# XMICRO-6502_V2_1.net
KiCad netlist of a schematic drawn in EAGLE
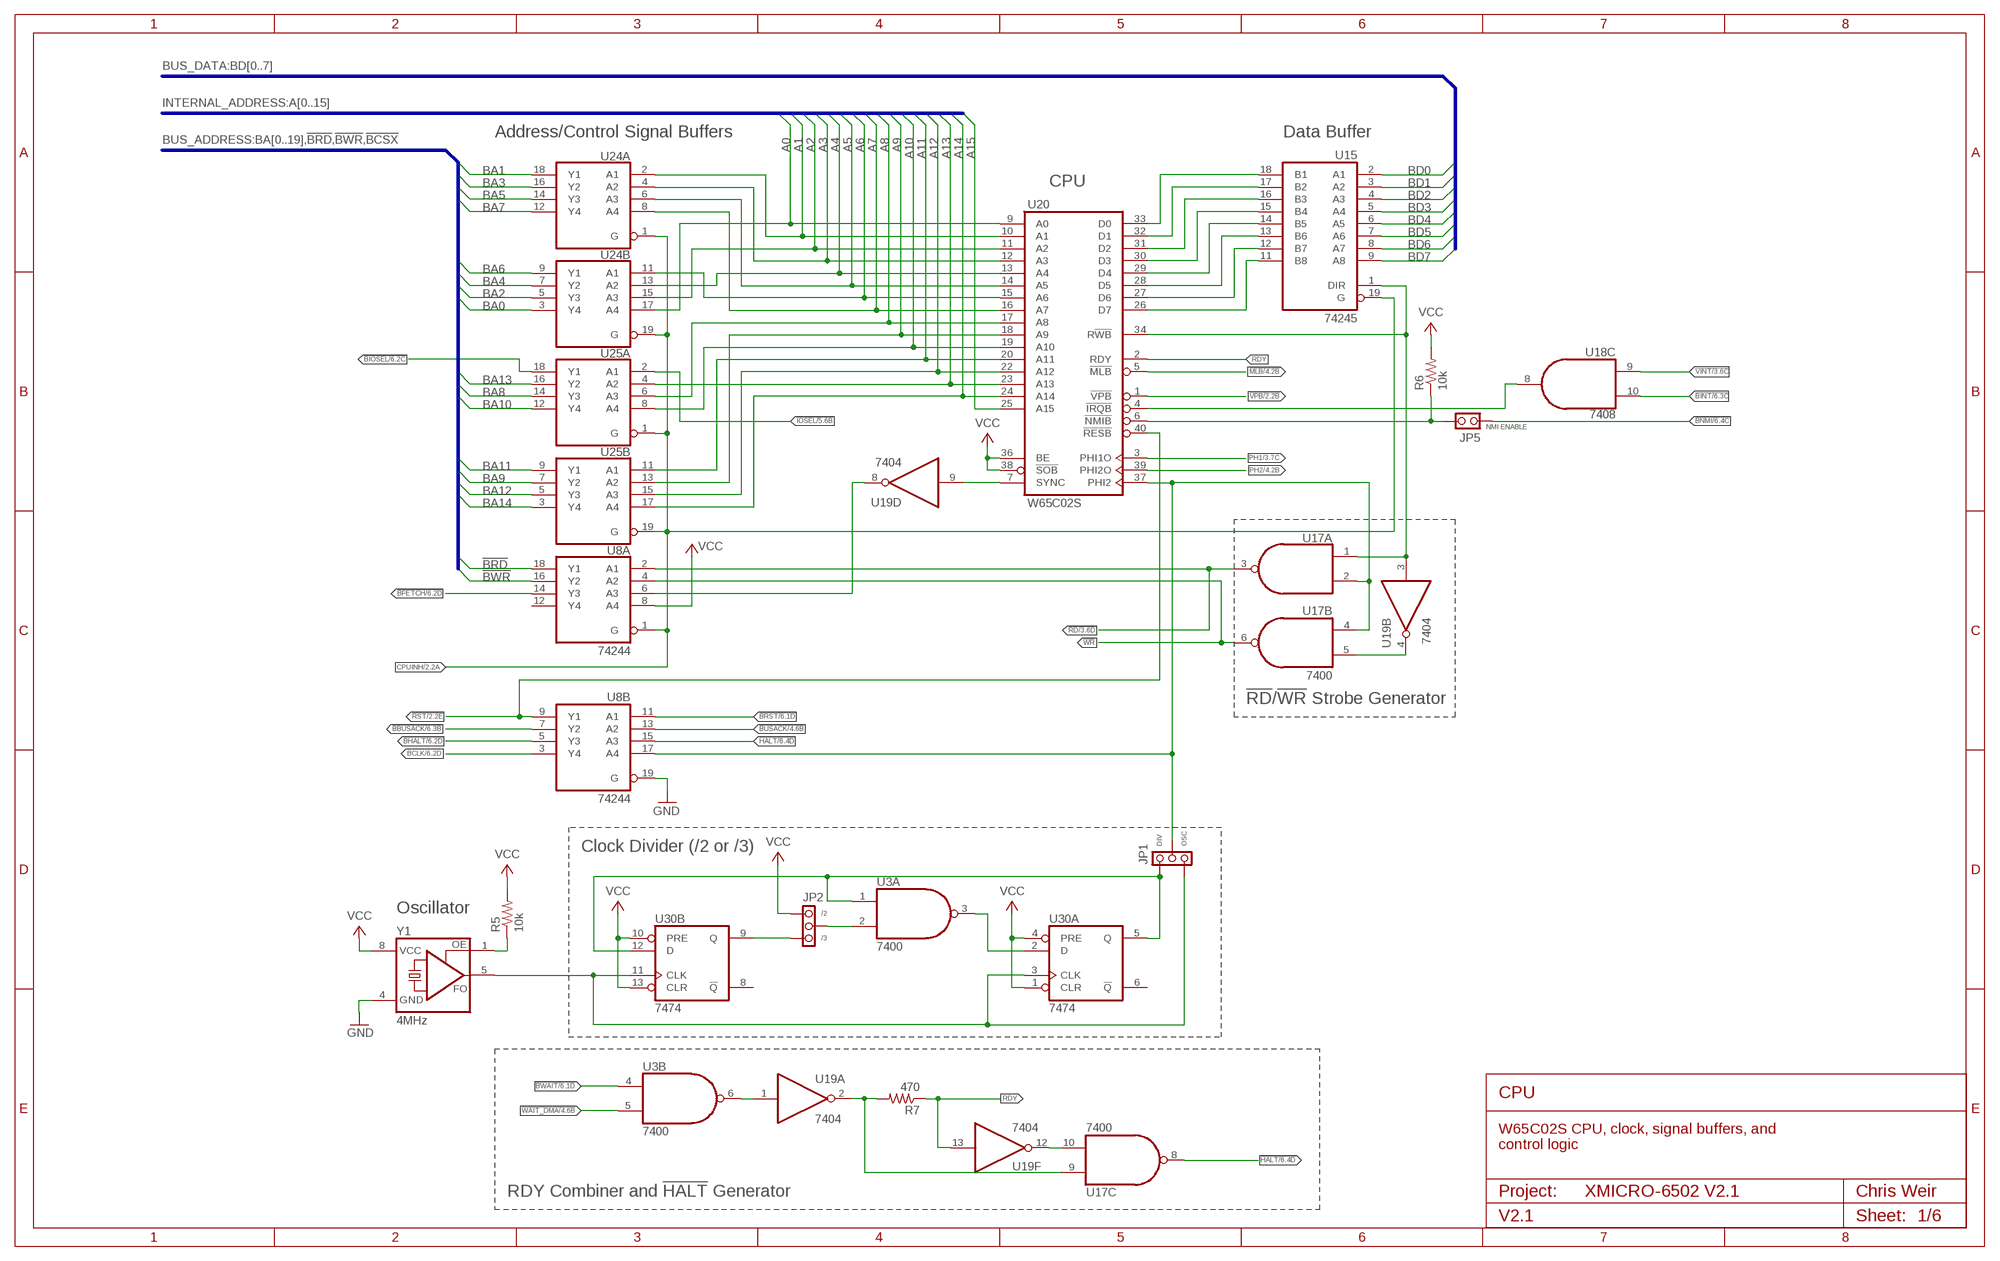
[diagram p0: schematic, sheet 1]
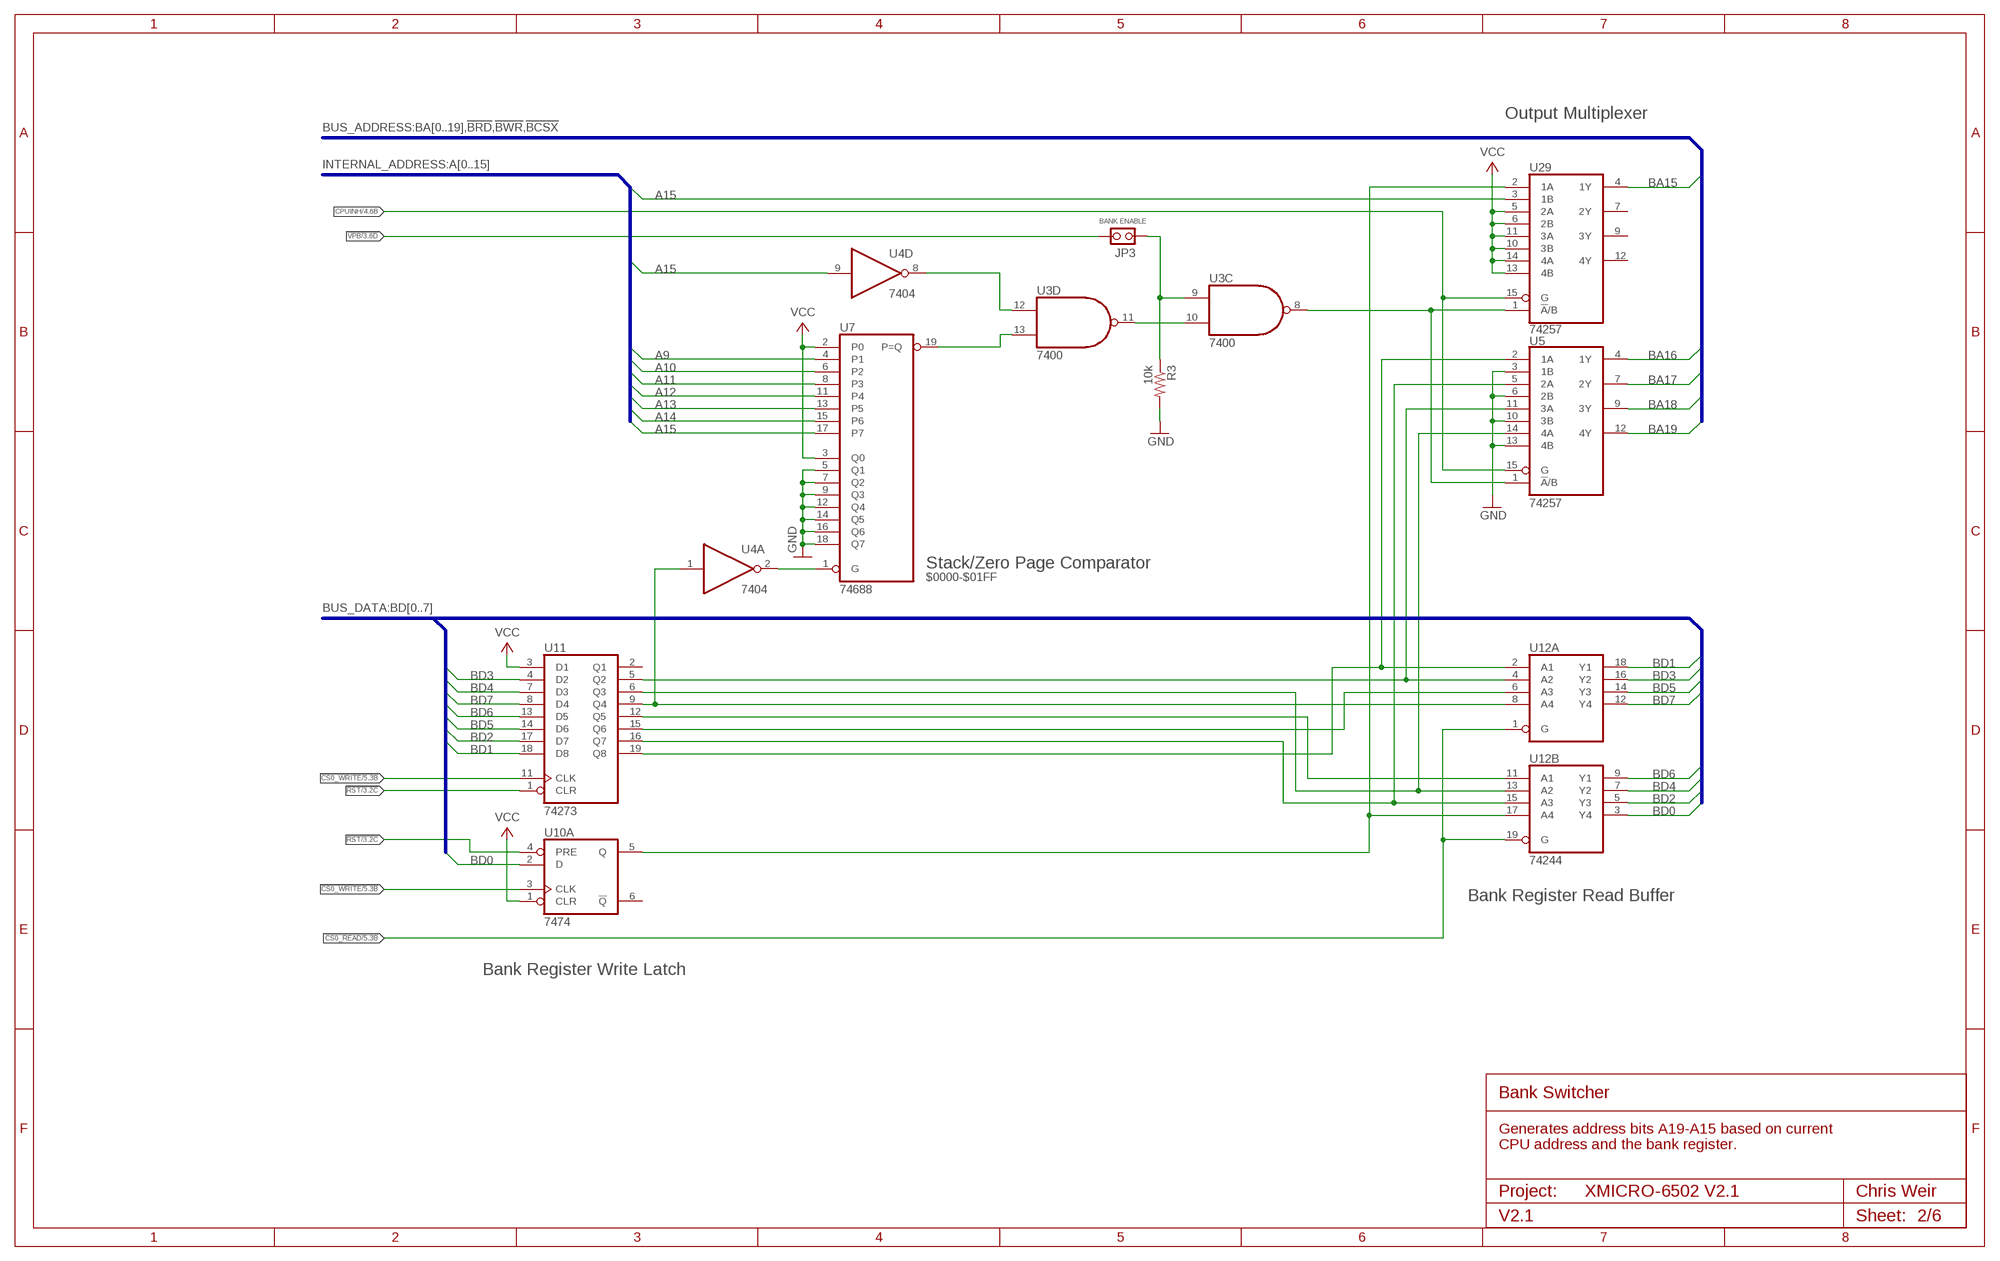
[diagram p1: schematic, sheet 2]
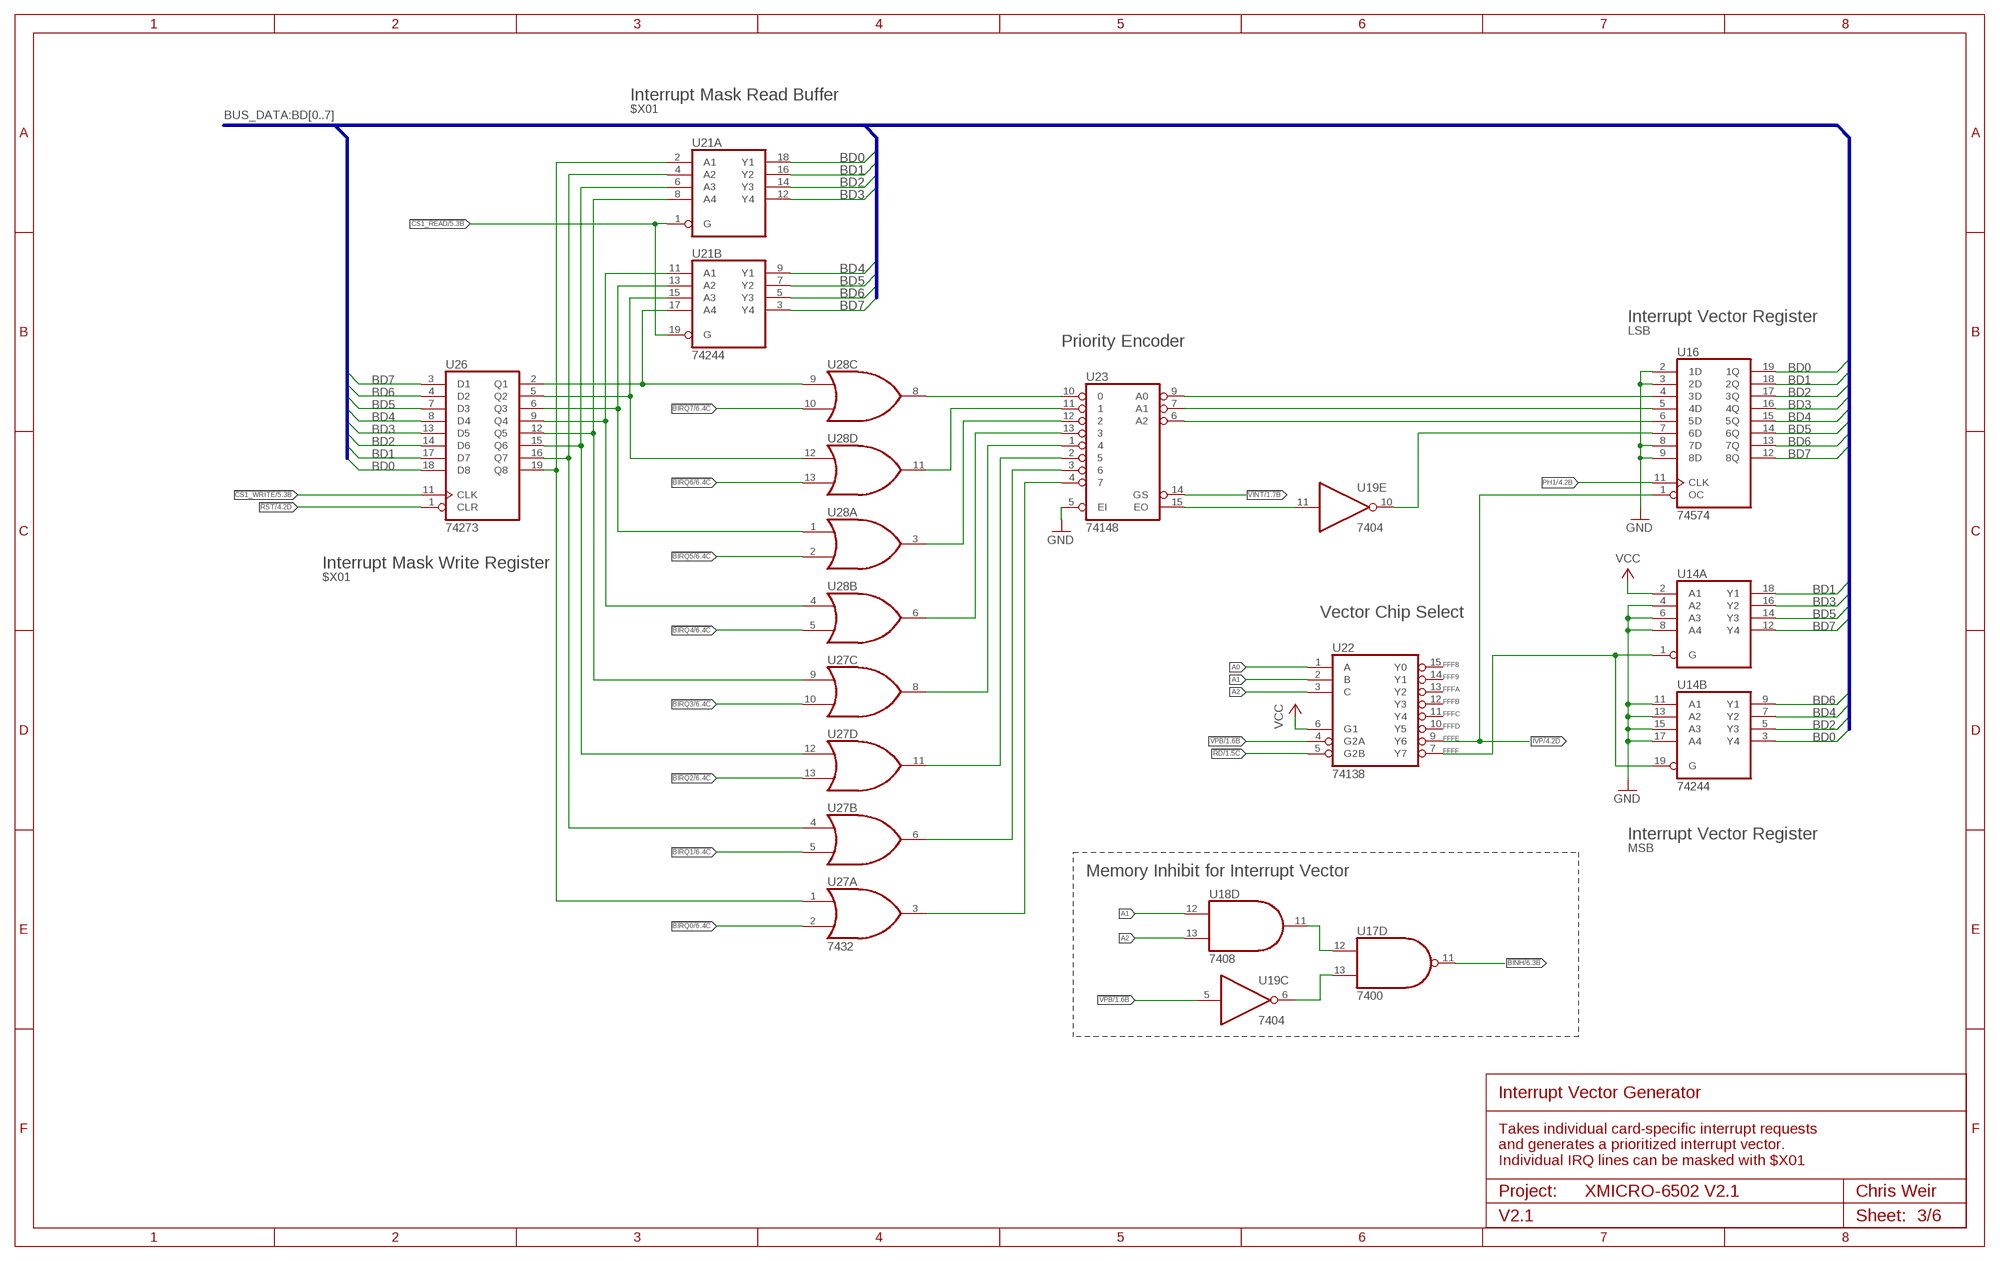
[diagram p2: schematic, sheet 3]
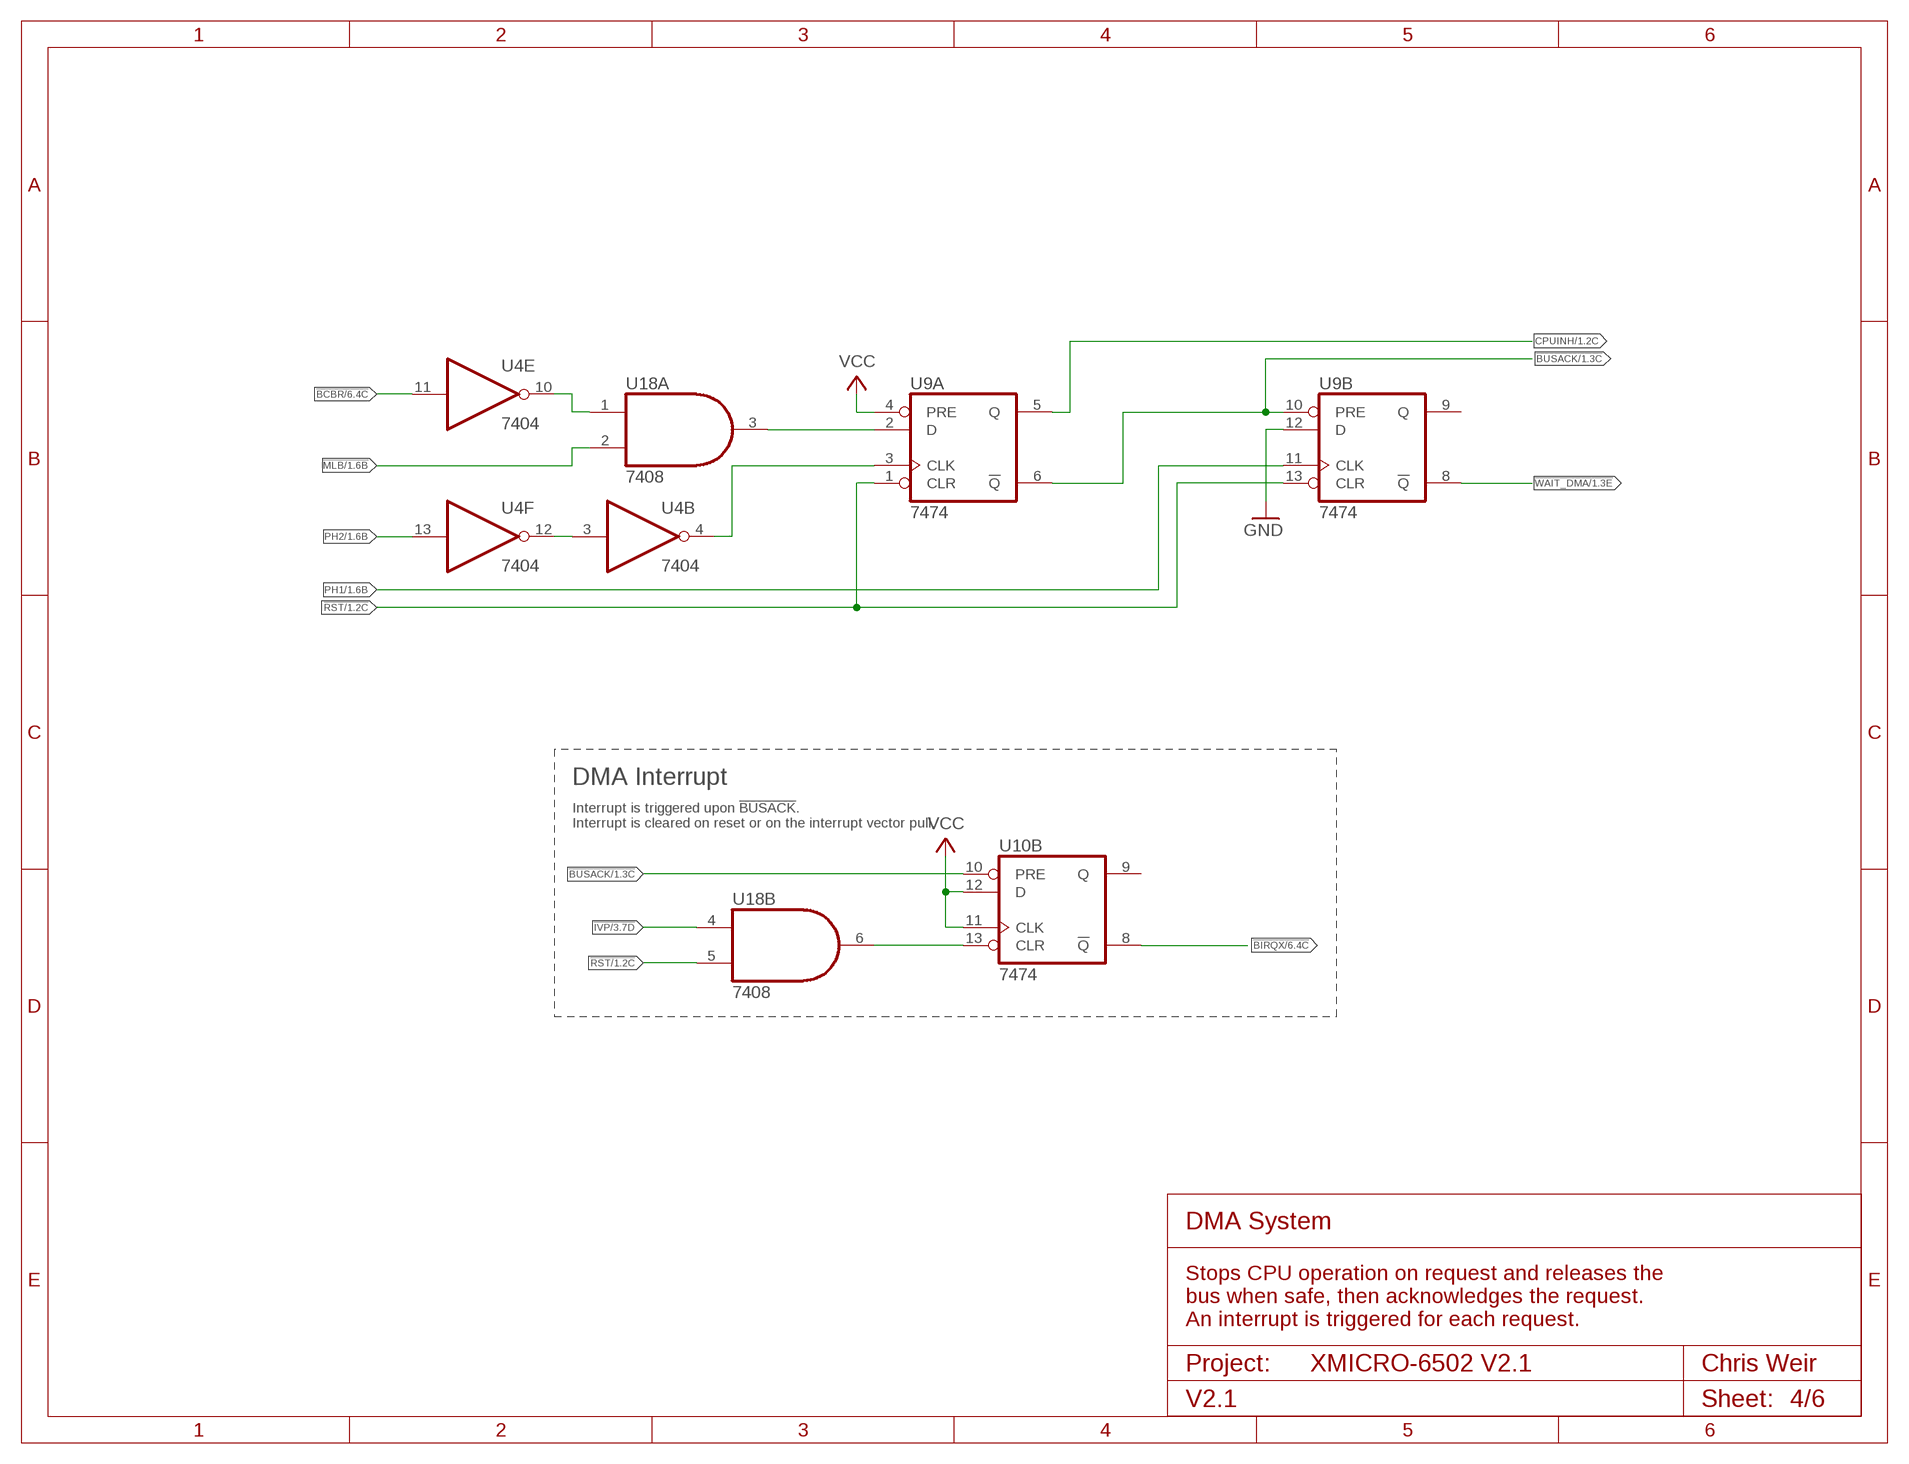
[diagram p3: schematic, sheet 4]
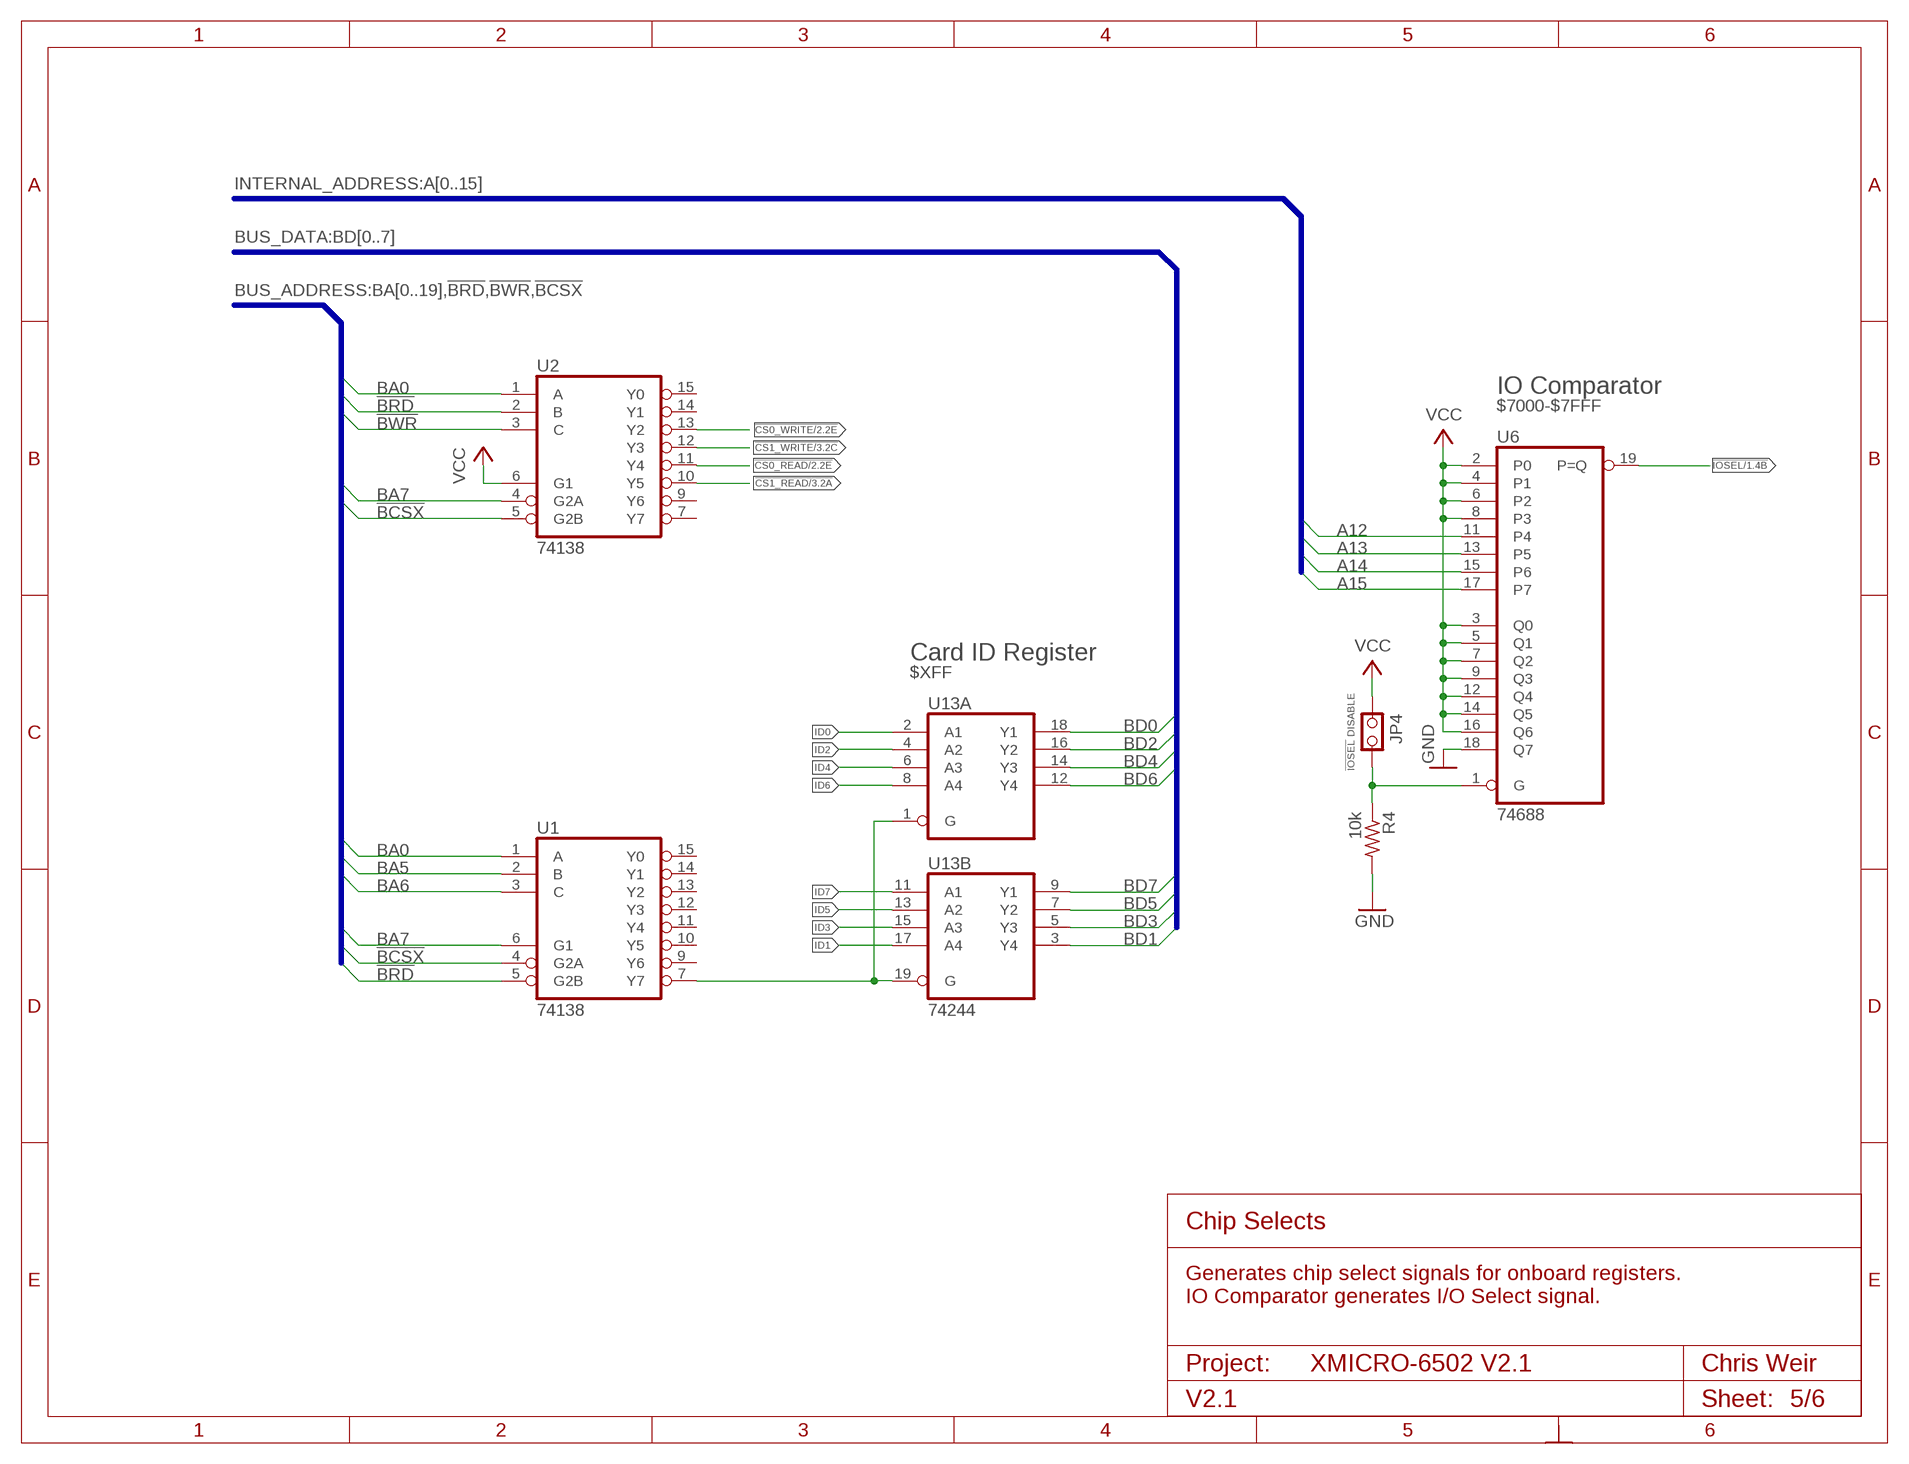
[diagram p4: schematic, sheet 5]
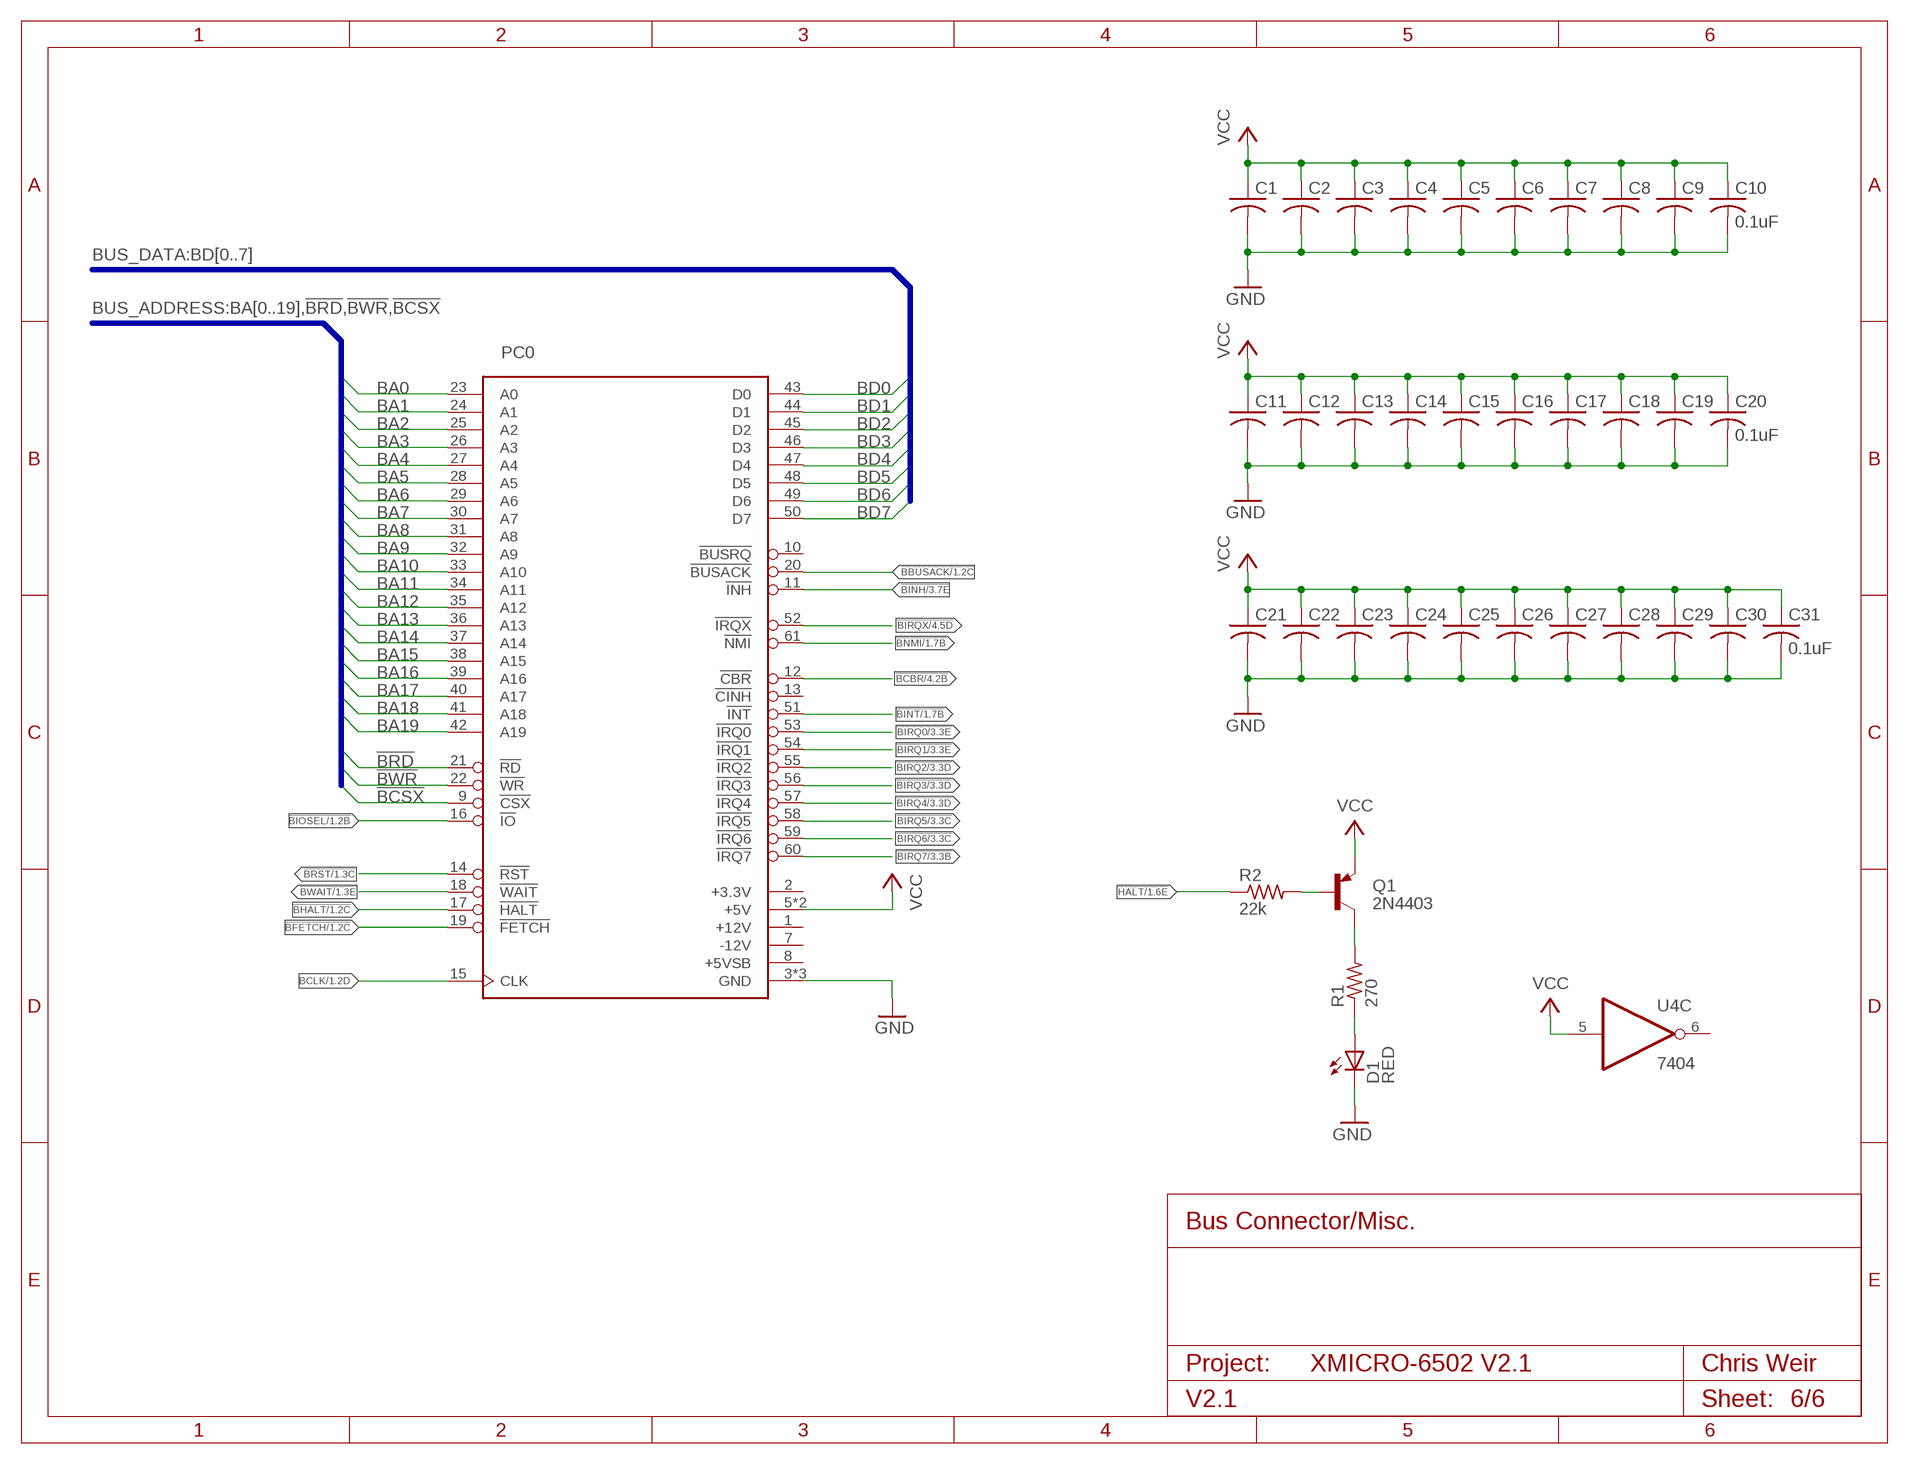
[diagram p5: schematic, sheet 6]

(export (version "E")
  (design (tool "Eeschema 10.0.6"))
  (components
    (comp (ref "JP3")
      (value "PINHD-1X2THRU")
      (footprint "eagle-import:1X02")
      (libsource (lib "eagle-import") (part "PINHD-1X2THRU"))
    )
    (comp (ref "R3")
      (value "10k")
      (footprint "eagle-import:0207_10")
      (libsource (lib "eagle-import") (part "R-US_0207/10"))
    )
    (comp (ref "U3")
      (value "7400")
      (footprint "eagle-import:DIL14")
      (libsource (lib "eagle-import") (part "7400NLS"))
    )
    (comp (ref "U4")
      (value "7404")
      (footprint "eagle-import:DIL14")
      (libsource (lib "eagle-import") (part "7404NLS"))
    )
    (comp (ref "U5")
      (value "74257")
      (footprint "eagle-import:DIL16")
      (libsource (lib "eagle-import") (part "74257NLS"))
    )
    (comp (ref "U7")
      (value "74688")
      (footprint "eagle-import:DIL20")
      (libsource (lib "eagle-import") (part "74688NLS"))
    )
    (comp (ref "U10")
      (value "7474")
      (footprint "eagle-import:DIL14")
      (libsource (lib "eagle-import") (part "7474NLS"))
    )
    (comp (ref "U11")
      (value "74273")
      (footprint "eagle-import:DIL20")
      (libsource (lib "eagle-import") (part "74273N"))
    )
    (comp (ref "U12")
      (value "74244")
      (footprint "eagle-import:DIL20")
      (libsource (lib "eagle-import") (part "74244NLS"))
    )
    (comp (ref "U29")
      (value "74257")
      (footprint "eagle-import:DIL16")
      (libsource (lib "eagle-import") (part "74257NLS"))
    )
    (comp (ref "JP1")
      (value "PINHD1X3THRU")
      (footprint "eagle-import:1X03")
      (libsource (lib "eagle-import") (part "PINHD1X3THRU"))
    )
    (comp (ref "JP2")
      (value "PINHD1X3THRU")
      (footprint "eagle-import:1X03")
      (libsource (lib "eagle-import") (part "PINHD1X3THRU"))
    )
    (comp (ref "JP5")
      (value "PINHD-1X2THRU")
      (footprint "eagle-import:1X02")
      (libsource (lib "eagle-import") (part "PINHD-1X2THRU"))
    )
    (comp (ref "R5")
      (value "10k")
      (footprint "eagle-import:0207_10")
      (libsource (lib "eagle-import") (part "R-US_0207/10"))
    )
    (comp (ref "R6")
      (value "10k")
      (footprint "eagle-import:0207_10")
      (libsource (lib "eagle-import") (part "R-US_0207/10"))
    )
    (comp (ref "R7")
      (value "470")
      (footprint "eagle-import:0207_10")
      (libsource (lib "eagle-import") (part "R-US_0207/10"))
    )
    (comp (ref "U8")
      (value "74244")
      (footprint "eagle-import:DIL20")
      (libsource (lib "eagle-import") (part "74244NLS"))
    )
    (comp (ref "U15")
      (value "74245")
      (footprint "eagle-import:DIL20")
      (libsource (lib "eagle-import") (part "74245NLS"))
    )
    (comp (ref "U17")
      (value "7400")
      (footprint "eagle-import:DIL14")
      (libsource (lib "eagle-import") (part "7400NLS"))
    )
    (comp (ref "U18")
      (value "7408")
      (footprint "eagle-import:DIL14")
      (libsource (lib "eagle-import") (part "7408NLS"))
    )
    (comp (ref "U19")
      (value "7404")
      (footprint "eagle-import:DIL14")
      (libsource (lib "eagle-import") (part "7404NLS"))
    )
    (comp (ref "U20")
      (value "W65C02S")
      (footprint "eagle-import:DIL40")
      (libsource (lib "eagle-import") (part "W65C02P"))
    )
    (comp (ref "U24")
      (value "74244")
      (footprint "eagle-import:DIL20")
      (libsource (lib "eagle-import") (part "74244NLS"))
    )
    (comp (ref "U25")
      (value "74244")
      (footprint "eagle-import:DIL20")
      (libsource (lib "eagle-import") (part "74244NLS"))
    )
    (comp (ref "U30")
      (value "7474")
      (footprint "eagle-import:DIL14")
      (libsource (lib "eagle-import") (part "7474NLS"))
    )
    (comp (ref "Y1")
      (value "4MHz")
      (footprint "eagle-import:DIL08S")
      (libsource (lib "eagle-import") (part "OSC-OE"))
    )
    (comp (ref "JP4")
      (value "PINHD-1X2THRU")
      (footprint "eagle-import:1X02")
      (libsource (lib "eagle-import") (part "PINHD-1X2THRU"))
    )
    (comp (ref "R4")
      (value "10k")
      (footprint "eagle-import:0207_10")
      (libsource (lib "eagle-import") (part "R-US_0207/10"))
    )
    (comp (ref "U1")
      (value "74138")
      (footprint "eagle-import:DIL16")
      (libsource (lib "eagle-import") (part "74138NLS"))
    )
    (comp (ref "U2")
      (value "74138")
      (footprint "eagle-import:DIL16")
      (libsource (lib "eagle-import") (part "74138NLS"))
    )
    (comp (ref "U6")
      (value "74688")
      (footprint "eagle-import:DIL20")
      (libsource (lib "eagle-import") (part "74688NLS"))
    )
    (comp (ref "U13")
      (value "74244")
      (footprint "eagle-import:DIL20")
      (libsource (lib "eagle-import") (part "74244NLS"))
    )
    (comp (ref "C1")
      (value "0.1uF")
      (footprint "eagle-import:C025-024X044")
      (libsource (lib "eagle-import") (part "C-US025-024X044"))
    )
    (comp (ref "C2")
      (value "0.1uF")
      (footprint "eagle-import:C025-024X044")
      (libsource (lib "eagle-import") (part "C-US025-024X044"))
    )
    (comp (ref "C3")
      (value "0.1uF")
      (footprint "eagle-import:C025-024X044")
      (libsource (lib "eagle-import") (part "C-US025-024X044"))
    )
    (comp (ref "C4")
      (value "0.1uF")
      (footprint "eagle-import:C025-024X044")
      (libsource (lib "eagle-import") (part "C-US025-024X044"))
    )
    (comp (ref "C5")
      (value "0.1uF")
      (footprint "eagle-import:C025-024X044")
      (libsource (lib "eagle-import") (part "C-US025-024X044"))
    )
    (comp (ref "C6")
      (value "0.1uF")
      (footprint "eagle-import:C025-024X044")
      (libsource (lib "eagle-import") (part "C-US025-024X044"))
    )
    (comp (ref "C7")
      (value "0.1uF")
      (footprint "eagle-import:C025-024X044")
      (libsource (lib "eagle-import") (part "C-US025-024X044"))
    )
    (comp (ref "C8")
      (value "0.1uF")
      (footprint "eagle-import:C025-024X044")
      (libsource (lib "eagle-import") (part "C-US025-024X044"))
    )
    (comp (ref "C9")
      (value "0.1uF")
      (footprint "eagle-import:C025-024X044")
      (libsource (lib "eagle-import") (part "C-US025-024X044"))
    )
    (comp (ref "C10")
      (value "0.1uF")
      (footprint "eagle-import:C025-024X044")
      (libsource (lib "eagle-import") (part "C-US025-024X044"))
    )
    (comp (ref "C11")
      (value "0.1uF")
      (footprint "eagle-import:C025-024X044")
      (libsource (lib "eagle-import") (part "C-US025-024X044"))
    )
    (comp (ref "C12")
      (value "0.1uF")
      (footprint "eagle-import:C025-024X044")
      (libsource (lib "eagle-import") (part "C-US025-024X044"))
    )
    (comp (ref "C13")
      (value "0.1uF")
      (footprint "eagle-import:C025-024X044")
      (libsource (lib "eagle-import") (part "C-US025-024X044"))
    )
    (comp (ref "C14")
      (value "0.1uF")
      (footprint "eagle-import:C025-024X044")
      (libsource (lib "eagle-import") (part "C-US025-024X044"))
    )
    (comp (ref "C15")
      (value "0.1uF")
      (footprint "eagle-import:C025-024X044")
      (libsource (lib "eagle-import") (part "C-US025-024X044"))
    )
    (comp (ref "C16")
      (value "0.1uF")
      (footprint "eagle-import:C025-024X044")
      (libsource (lib "eagle-import") (part "C-US025-024X044"))
    )
    (comp (ref "C17")
      (value "0.1uF")
      (footprint "eagle-import:C025-024X044")
      (libsource (lib "eagle-import") (part "C-US025-024X044"))
    )
    (comp (ref "C18")
      (value "0.1uF")
      (footprint "eagle-import:C025-024X044")
      (libsource (lib "eagle-import") (part "C-US025-024X044"))
    )
    (comp (ref "C19")
      (value "0.1uF")
      (footprint "eagle-import:C025-024X044")
      (libsource (lib "eagle-import") (part "C-US025-024X044"))
    )
    (comp (ref "C20")
      (value "0.1uF")
      (footprint "eagle-import:C025-024X044")
      (libsource (lib "eagle-import") (part "C-US025-024X044"))
    )
    (comp (ref "C21")
      (value "0.1uF")
      (footprint "eagle-import:C025-024X044")
      (libsource (lib "eagle-import") (part "C-US025-024X044"))
    )
    (comp (ref "C22")
      (value "0.1uF")
      (footprint "eagle-import:C025-024X044")
      (libsource (lib "eagle-import") (part "C-US025-024X044"))
    )
    (comp (ref "C23")
      (value "0.1uF")
      (footprint "eagle-import:C025-024X044")
      (libsource (lib "eagle-import") (part "C-US025-024X044"))
    )
    (comp (ref "C24")
      (value "0.1uF")
      (footprint "eagle-import:C025-024X044")
      (libsource (lib "eagle-import") (part "C-US025-024X044"))
    )
    (comp (ref "C25")
      (value "0.1uF")
      (footprint "eagle-import:C025-024X044")
      (libsource (lib "eagle-import") (part "C-US025-024X044"))
    )
    (comp (ref "C26")
      (value "0.1uF")
      (footprint "eagle-import:C025-024X044")
      (libsource (lib "eagle-import") (part "C-US025-024X044"))
    )
    (comp (ref "C27")
      (value "0.1uF")
      (footprint "eagle-import:C025-024X044")
      (libsource (lib "eagle-import") (part "C-US025-024X044"))
    )
    (comp (ref "C28")
      (value "0.1uF")
      (footprint "eagle-import:C025-024X044")
      (libsource (lib "eagle-import") (part "C-US025-024X044"))
    )
    (comp (ref "C29")
      (value "0.1uF")
      (footprint "eagle-import:C025-024X044")
      (libsource (lib "eagle-import") (part "C-US025-024X044"))
    )
    (comp (ref "C30")
      (value "0.1uF")
      (footprint "eagle-import:C025-024X044")
      (libsource (lib "eagle-import") (part "C-US025-024X044"))
    )
    (comp (ref "C31")
      (value "0.1uF")
      (footprint "eagle-import:C025-024X044")
      (libsource (lib "eagle-import") (part "C-US025-024X044"))
    )
    (comp (ref "D1")
      (value "RED")
      (footprint "eagle-import:LED5MM")
      (libsource (lib "eagle-import") (part "LED5MM"))
    )
    (comp (ref "PC0")
      (value "XMICRO-BUS-EDGE62M")
      (footprint "eagle-import:EDGE62M")
      (libsource (lib "eagle-import") (part "XMICRO-BUS-EDGE62M"))
    )
    (comp (ref "Q1")
      (value "2N4403")
      (footprint "eagle-import:TO92")
      (libsource (lib "eagle-import") (part "TRANSISTOR-PNP-2N4403"))
    )
    (comp (ref "R1")
      (value "270")
      (footprint "eagle-import:0207_10")
      (libsource (lib "eagle-import") (part "R-US_0207/10"))
    )
    (comp (ref "R2")
      (value "22k")
      (footprint "eagle-import:0207_10")
      (libsource (lib "eagle-import") (part "R-US_0207/10"))
    )
    (comp (ref "U14")
      (value "74244")
      (footprint "eagle-import:DIL20")
      (libsource (lib "eagle-import") (part "74244NLS"))
    )
    (comp (ref "U16")
      (value "74574")
      (footprint "eagle-import:DIL20")
      (libsource (lib "eagle-import") (part "74574NHC"))
    )
    (comp (ref "U21")
      (value "74244")
      (footprint "eagle-import:DIL20")
      (libsource (lib "eagle-import") (part "74244NLS"))
    )
    (comp (ref "U22")
      (value "74138")
      (footprint "eagle-import:DIL16")
      (libsource (lib "eagle-import") (part "74138NLS"))
    )
    (comp (ref "U23")
      (value "74148")
      (footprint "eagle-import:DIL16")
      (libsource (lib "eagle-import") (part "74148NLS"))
    )
    (comp (ref "U26")
      (value "74273")
      (footprint "eagle-import:DIL20")
      (libsource (lib "eagle-import") (part "74273N"))
    )
    (comp (ref "U27")
      (value "7432")
      (footprint "eagle-import:DIL14")
      (libsource (lib "eagle-import") (part "7432NLS"))
    )
    (comp (ref "U28")
      (value "7432")
      (footprint "eagle-import:DIL14")
      (libsource (lib "eagle-import") (part "7432NLS"))
    )
    (comp (ref "U9")
      (value "7474")
      (footprint "eagle-import:DIL14")
      (libsource (lib "eagle-import") (part "7474NLS"))
    )
  )
  (nets
    (net (code "105") (name "A0") (class "Default")
      (node (ref "U20") (pin "9") (pinfunction "A0_9") (pintype "output"))
      (node (ref "U22") (pin "1") (pinfunction "A_1") (pintype "input"))
      (node (ref "U24") (pin "17") (pinfunction "A4_17") (pintype "input"))
    )
    (net (code "106") (name "A1") (class "Default")
      (node (ref "U18") (pin "12") (pinfunction "I0_12") (pintype "input"))
      (node (ref "U20") (pin "10") (pinfunction "A1_10") (pintype "output"))
      (node (ref "U22") (pin "2") (pinfunction "B_2") (pintype "input"))
      (node (ref "U24") (pin "2") (pinfunction "A1_2") (pintype "input"))
    )
    (net (code "107") (name "A2") (class "Default")
      (node (ref "U18") (pin "13") (pinfunction "I1_13") (pintype "input"))
      (node (ref "U20") (pin "11") (pinfunction "A2_11") (pintype "output"))
      (node (ref "U22") (pin "3") (pinfunction "C_3") (pintype "input"))
      (node (ref "U24") (pin "15") (pinfunction "A3_15") (pintype "input"))
    )
    (net (code "108") (name "A3") (class "Default")
      (node (ref "U20") (pin "12") (pinfunction "A3_12") (pintype "output"))
      (node (ref "U24") (pin "4") (pinfunction "A2_4") (pintype "input"))
    )
    (net (code "109") (name "A4") (class "Default")
      (node (ref "U20") (pin "13") (pinfunction "A4_13") (pintype "output"))
      (node (ref "U24") (pin "13") (pinfunction "A2_13") (pintype "input"))
    )
    (net (code "110") (name "A5") (class "Default")
      (node (ref "U20") (pin "14") (pinfunction "A5_14") (pintype "output"))
      (node (ref "U24") (pin "6") (pinfunction "A3_6") (pintype "input"))
    )
    (net (code "111") (name "A6") (class "Default")
      (node (ref "U20") (pin "15") (pinfunction "A6_15") (pintype "output"))
      (node (ref "U24") (pin "11") (pinfunction "A1_11") (pintype "input"))
    )
    (net (code "112") (name "A7") (class "Default")
      (node (ref "U20") (pin "16") (pinfunction "A7_16") (pintype "output"))
      (node (ref "U24") (pin "8") (pinfunction "A4_8") (pintype "input"))
    )
    (net (code "113") (name "A8") (class "Default")
      (node (ref "U20") (pin "17") (pinfunction "A8_17") (pintype "output"))
      (node (ref "U25") (pin "6") (pinfunction "A3_6") (pintype "input"))
    )
    (net (code "114") (name "A9") (class "Default")
      (node (ref "U20") (pin "18") (pinfunction "A9_18") (pintype "output"))
      (node (ref "U25") (pin "13") (pinfunction "A2_13") (pintype "input"))
      (node (ref "U7") (pin "4") (pinfunction "P1_4") (pintype "input"))
    )
    (net (code "115") (name "A10") (class "Default")
      (node (ref "U20") (pin "19") (pinfunction "A10_19") (pintype "output"))
      (node (ref "U25") (pin "8") (pinfunction "A4_8") (pintype "input"))
      (node (ref "U7") (pin "6") (pinfunction "P2_6") (pintype "input"))
    )
    (net (code "116") (name "A11") (class "Default")
      (node (ref "U20") (pin "20") (pinfunction "A11_20") (pintype "output"))
      (node (ref "U25") (pin "11") (pinfunction "A1_11") (pintype "input"))
      (node (ref "U7") (pin "8") (pinfunction "P3_8") (pintype "input"))
    )
    (net (code "117") (name "A12") (class "Default")
      (node (ref "U20") (pin "22") (pinfunction "A12_22") (pintype "output"))
      (node (ref "U25") (pin "15") (pinfunction "A3_15") (pintype "input"))
      (node (ref "U6") (pin "11") (pinfunction "P4_11") (pintype "input"))
      (node (ref "U7") (pin "11") (pinfunction "P4_11") (pintype "input"))
    )
    (net (code "118") (name "A13") (class "Default")
      (node (ref "U20") (pin "23") (pinfunction "A13_23") (pintype "output"))
      (node (ref "U25") (pin "4") (pinfunction "A2_4") (pintype "input"))
      (node (ref "U6") (pin "13") (pinfunction "P5_13") (pintype "input"))
      (node (ref "U7") (pin "13") (pinfunction "P5_13") (pintype "input"))
    )
    (net (code "119") (name "A14") (class "Default")
      (node (ref "U20") (pin "24") (pinfunction "A14_24") (pintype "output"))
      (node (ref "U25") (pin "17") (pinfunction "A4_17") (pintype "input"))
      (node (ref "U6") (pin "15") (pinfunction "P6_15") (pintype "input"))
      (node (ref "U7") (pin "15") (pinfunction "P6_15") (pintype "input"))
    )
    (net (code "120") (name "A15") (class "Default")
      (node (ref "U20") (pin "25") (pinfunction "A15_25") (pintype "output"))
      (node (ref "U29") (pin "3") (pinfunction "1B_3") (pintype "input"))
      (node (ref "U4") (pin "9") (pinfunction "I_9") (pintype "input"))
      (node (ref "U6") (pin "17") (pinfunction "P7_17") (pintype "input"))
      (node (ref "U7") (pin "17") (pinfunction "P7_17") (pintype "input"))
    )
    (net (code "121") (name "BA0") (class "Default")
      (node (ref "PC0") (pin "23") (pinfunction "A0_23") (pintype "bidirectional"))
      (node (ref "U1") (pin "1") (pinfunction "A_1") (pintype "input"))
      (node (ref "U2") (pin "1") (pinfunction "A_1") (pintype "input"))
      (node (ref "U24") (pin "3") (pinfunction "Y4_3") (pintype "tri_state"))
    )
    (net (code "122") (name "BA1") (class "Default")
      (node (ref "PC0") (pin "24") (pinfunction "A1_24") (pintype "bidirectional"))
      (node (ref "U24") (pin "18") (pinfunction "Y1_18") (pintype "tri_state"))
    )
    (net (code "123") (name "BA2") (class "Default")
      (node (ref "PC0") (pin "25") (pinfunction "A2_25") (pintype "bidirectional"))
      (node (ref "U24") (pin "5") (pinfunction "Y3_5") (pintype "tri_state"))
    )
    (net (code "124") (name "BA3") (class "Default")
      (node (ref "PC0") (pin "26") (pinfunction "A3_26") (pintype "bidirectional"))
      (node (ref "U24") (pin "16") (pinfunction "Y2_16") (pintype "tri_state"))
    )
    (net (code "125") (name "BA4") (class "Default")
      (node (ref "PC0") (pin "27") (pinfunction "A4_27") (pintype "bidirectional"))
      (node (ref "U24") (pin "7") (pinfunction "Y2_7") (pintype "tri_state"))
    )
    (net (code "126") (name "BA5") (class "Default")
      (node (ref "PC0") (pin "28") (pinfunction "A5_28") (pintype "bidirectional"))
      (node (ref "U1") (pin "2") (pinfunction "B_2") (pintype "input"))
      (node (ref "U24") (pin "14") (pinfunction "Y3_14") (pintype "tri_state"))
    )
    (net (code "127") (name "BA6") (class "Default")
      (node (ref "PC0") (pin "29") (pinfunction "A6_29") (pintype "bidirectional"))
      (node (ref "U1") (pin "3") (pinfunction "C_3") (pintype "input"))
      (node (ref "U24") (pin "9") (pinfunction "Y1_9") (pintype "tri_state"))
    )
    (net (code "128") (name "BA7") (class "Default")
      (node (ref "PC0") (pin "30") (pinfunction "A7_30") (pintype "bidirectional"))
      (node (ref "U1") (pin "6") (pinfunction "G1_6") (pintype "input"))
      (node (ref "U2") (pin "4") (pinfunction "G2A_4") (pintype "input"))
      (node (ref "U24") (pin "12") (pinfunction "Y4_12") (pintype "tri_state"))
    )
    (net (code "129") (name "BA8") (class "Default")
      (node (ref "PC0") (pin "31") (pinfunction "A8_31") (pintype "bidirectional"))
      (node (ref "U25") (pin "14") (pinfunction "Y3_14") (pintype "tri_state"))
    )
    (net (code "130") (name "BA9") (class "Default")
      (node (ref "PC0") (pin "32") (pinfunction "A9_32") (pintype "bidirectional"))
      (node (ref "U25") (pin "7") (pinfunction "Y2_7") (pintype "tri_state"))
    )
    (net (code "131") (name "BA10") (class "Default")
      (node (ref "PC0") (pin "33") (pinfunction "A10_33") (pintype "bidirectional"))
      (node (ref "U25") (pin "12") (pinfunction "Y4_12") (pintype "tri_state"))
    )
    (net (code "132") (name "BA11") (class "Default")
      (node (ref "PC0") (pin "34") (pinfunction "A11_34") (pintype "bidirectional"))
      (node (ref "U25") (pin "9") (pinfunction "Y1_9") (pintype "tri_state"))
    )
    (net (code "133") (name "BA12") (class "Default")
      (node (ref "PC0") (pin "35") (pinfunction "A12_35") (pintype "bidirectional"))
      (node (ref "U25") (pin "5") (pinfunction "Y3_5") (pintype "tri_state"))
    )
    (net (code "134") (name "BA13") (class "Default")
      (node (ref "PC0") (pin "36") (pinfunction "A13_36") (pintype "bidirectional"))
      (node (ref "U25") (pin "16") (pinfunction "Y2_16") (pintype "tri_state"))
    )
    (net (code "135") (name "BA14") (class "Default")
      (node (ref "PC0") (pin "37") (pinfunction "A14_37") (pintype "bidirectional"))
      (node (ref "U25") (pin "3") (pinfunction "Y4_3") (pintype "tri_state"))
    )
    (net (code "136") (name "BA15") (class "Default")
      (node (ref "PC0") (pin "38") (pinfunction "A15_38") (pintype "bidirectional"))
      (node (ref "U29") (pin "4") (pinfunction "1Y_4") (pintype "tri_state"))
    )
    (net (code "137") (name "BA16") (class "Default")
      (node (ref "PC0") (pin "39") (pinfunction "A16_39") (pintype "bidirectional"))
      (node (ref "U5") (pin "4") (pinfunction "1Y_4") (pintype "tri_state"))
    )
    (net (code "138") (name "BA17") (class "Default")
      (node (ref "PC0") (pin "40") (pinfunction "A17_40") (pintype "bidirectional"))
      (node (ref "U5") (pin "7") (pinfunction "2Y_7") (pintype "tri_state"))
    )
    (net (code "139") (name "BA18") (class "Default")
      (node (ref "PC0") (pin "41") (pinfunction "A18_41") (pintype "bidirectional"))
      (node (ref "U5") (pin "9") (pinfunction "3Y_9") (pintype "tri_state"))
    )
    (net (code "140") (name "BA19") (class "Default")
      (node (ref "PC0") (pin "42") (pinfunction "A19_42") (pintype "bidirectional"))
      (node (ref "U5") (pin "12") (pinfunction "4Y_12") (pintype "tri_state"))
    )
    (net (code "141") (name "BCLK") (class "Default")
      (node (ref "PC0") (pin "15") (pinfunction "CLK_15") (pintype "bidirectional"))
      (node (ref "U8") (pin "3") (pinfunction "Y4_3") (pintype "tri_state"))
    )
    (net (code "142") (name "BD0") (class "Default")
      (node (ref "PC0") (pin "43") (pinfunction "D0_43") (pintype "bidirectional"))
      (node (ref "U10") (pin "2") (pinfunction "D_2") (pintype "input"))
      (node (ref "U12") (pin "3") (pinfunction "Y4_3") (pintype "tri_state"))
      (node (ref "U13") (pin "18") (pinfunction "Y1_18") (pintype "tri_state"))
      (node (ref "U14") (pin "3") (pinfunction "Y4_3") (pintype "tri_state"))
      (node (ref "U15") (pin "2") (pinfunction "A1_2") (pintype "bidirectional"))
      (node (ref "U16") (pin "19") (pinfunction "1Q_19") (pintype "tri_state"))
      (node (ref "U21") (pin "18") (pinfunction "Y1_18") (pintype "tri_state"))
      (node (ref "U26") (pin "18") (pinfunction "D8_18") (pintype "input"))
    )
    (net (code "143") (name "BD1") (class "Default")
      (node (ref "PC0") (pin "44") (pinfunction "D1_44") (pintype "bidirectional"))
      (node (ref "U11") (pin "18") (pinfunction "D8_18") (pintype "input"))
      (node (ref "U12") (pin "18") (pinfunction "Y1_18") (pintype "tri_state"))
      (node (ref "U13") (pin "3") (pinfunction "Y4_3") (pintype "tri_state"))
      (node (ref "U14") (pin "18") (pinfunction "Y1_18") (pintype "tri_state"))
      (node (ref "U15") (pin "3") (pinfunction "A2_3") (pintype "bidirectional"))
      (node (ref "U16") (pin "18") (pinfunction "2Q_18") (pintype "tri_state"))
      (node (ref "U21") (pin "16") (pinfunction "Y2_16") (pintype "tri_state"))
      (node (ref "U26") (pin "17") (pinfunction "D7_17") (pintype "input"))
    )
    (net (code "144") (name "BD2") (class "Default")
      (node (ref "PC0") (pin "45") (pinfunction "D2_45") (pintype "bidirectional"))
      (node (ref "U11") (pin "17") (pinfunction "D7_17") (pintype "input"))
      (node (ref "U12") (pin "5") (pinfunction "Y3_5") (pintype "tri_state"))
      (node (ref "U13") (pin "16") (pinfunction "Y2_16") (pintype "tri_state"))
      (node (ref "U14") (pin "5") (pinfunction "Y3_5") (pintype "tri_state"))
      (node (ref "U15") (pin "4") (pinfunction "A3_4") (pintype "bidirectional"))
      (node (ref "U16") (pin "17") (pinfunction "3Q_17") (pintype "tri_state"))
      (node (ref "U21") (pin "14") (pinfunction "Y3_14") (pintype "tri_state"))
      (node (ref "U26") (pin "14") (pinfunction "D6_14") (pintype "input"))
    )
    (net (code "145") (name "BD3") (class "Default")
      (node (ref "PC0") (pin "46") (pinfunction "D3_46") (pintype "bidirectional"))
      (node (ref "U11") (pin "4") (pinfunction "D2_4") (pintype "input"))
      (node (ref "U12") (pin "16") (pinfunction "Y2_16") (pintype "tri_state"))
      (node (ref "U13") (pin "5") (pinfunction "Y3_5") (pintype "tri_state"))
      (node (ref "U14") (pin "16") (pinfunction "Y2_16") (pintype "tri_state"))
      (node (ref "U15") (pin "5") (pinfunction "A4_5") (pintype "bidirectional"))
      (node (ref "U16") (pin "16") (pinfunction "4Q_16") (pintype "tri_state"))
      (node (ref "U21") (pin "12") (pinfunction "Y4_12") (pintype "tri_state"))
      (node (ref "U26") (pin "13") (pinfunction "D5_13") (pintype "input"))
    )
    (net (code "146") (name "BD4") (class "Default")
      (node (ref "PC0") (pin "47") (pinfunction "D4_47") (pintype "bidirectional"))
      (node (ref "U11") (pin "7") (pinfunction "D3_7") (pintype "input"))
      (node (ref "U12") (pin "7") (pinfunction "Y2_7") (pintype "tri_state"))
      (node (ref "U13") (pin "14") (pinfunction "Y3_14") (pintype "tri_state"))
      (node (ref "U14") (pin "7") (pinfunction "Y2_7") (pintype "tri_state"))
      (node (ref "U15") (pin "6") (pinfunction "A5_6") (pintype "bidirectional"))
      (node (ref "U16") (pin "15") (pinfunction "5Q_15") (pintype "tri_state"))
      (node (ref "U21") (pin "9") (pinfunction "Y1_9") (pintype "tri_state"))
      (node (ref "U26") (pin "8") (pinfunction "D4_8") (pintype "input"))
    )
    (net (code "147") (name "BD5") (class "Default")
      (node (ref "PC0") (pin "48") (pinfunction "D5_48") (pintype "bidirectional"))
      (node (ref "U11") (pin "14") (pinfunction "D6_14") (pintype "input"))
      (node (ref "U12") (pin "14") (pinfunction "Y3_14") (pintype "tri_state"))
      (node (ref "U13") (pin "7") (pinfunction "Y2_7") (pintype "tri_state"))
      (node (ref "U14") (pin "14") (pinfunction "Y3_14") (pintype "tri_state"))
      (node (ref "U15") (pin "7") (pinfunction "A6_7") (pintype "bidirectional"))
      (node (ref "U16") (pin "14") (pinfunction "6Q_14") (pintype "tri_state"))
      (node (ref "U21") (pin "7") (pinfunction "Y2_7") (pintype "tri_state"))
      (node (ref "U26") (pin "7") (pinfunction "D3_7") (pintype "input"))
    )
    (net (code "148") (name "BD6") (class "Default")
      (node (ref "PC0") (pin "49") (pinfunction "D6_49") (pintype "bidirectional"))
      (node (ref "U11") (pin "13") (pinfunction "D5_13") (pintype "input"))
      (node (ref "U12") (pin "9") (pinfunction "Y1_9") (pintype "tri_state"))
      (node (ref "U13") (pin "12") (pinfunction "Y4_12") (pintype "tri_state"))
      (node (ref "U14") (pin "9") (pinfunction "Y1_9") (pintype "tri_state"))
      (node (ref "U15") (pin "8") (pinfunction "A7_8") (pintype "bidirectional"))
      (node (ref "U16") (pin "13") (pinfunction "7Q_13") (pintype "tri_state"))
      (node (ref "U21") (pin "5") (pinfunction "Y3_5") (pintype "tri_state"))
      (node (ref "U26") (pin "4") (pinfunction "D2_4") (pintype "input"))
    )
    (net (code "149") (name "BD7") (class "Default")
      (node (ref "PC0") (pin "50") (pinfunction "D7_50") (pintype "bidirectional"))
      (node (ref "U11") (pin "8") (pinfunction "D4_8") (pintype "input"))
      (node (ref "U12") (pin "12") (pinfunction "Y4_12") (pintype "tri_state"))
      (node (ref "U13") (pin "9") (pinfunction "Y1_9") (pintype "tri_state"))
      (node (ref "U14") (pin "12") (pinfunction "Y4_12") (pintype "tri_state"))
      (node (ref "U15") (pin "9") (pinfunction "A8_9") (pintype "bidirectional"))
      (node (ref "U16") (pin "12") (pinfunction "8Q_12") (pintype "tri_state"))
      (node (ref "U21") (pin "3") (pinfunction "Y4_3") (pintype "tri_state"))
      (node (ref "U26") (pin "3") (pinfunction "D1_3") (pintype "input"))
    )
    (net (code "150") (name "CPUINH") (class "Default")
      (node (ref "U15") (pin "19") (pinfunction "G_19") (pintype "input"))
      (node (ref "U24") (pin "1") (pinfunction "G_1") (pintype "input"))
      (node (ref "U24") (pin "19") (pinfunction "G_19") (pintype "input"))
      (node (ref "U25") (pin "1") (pinfunction "G_1") (pintype "input"))
      (node (ref "U25") (pin "19") (pinfunction "G_19") (pintype "input"))
      (node (ref "U29") (pin "15") (pinfunction "G_15") (pintype "input"))
      (node (ref "U5") (pin "15") (pinfunction "G_15") (pintype "input"))
      (node (ref "U8") (pin "1") (pinfunction "G_1") (pintype "input"))
      (node (ref "U9") (pin "5") (pinfunction "Q_5") (pintype "output"))
    )
    (net (code "151") (name "GND") (class "Default")
      (node (ref "C1") (pin "2") (pinfunction "2_2") (pintype "passive"))
      (node (ref "C10") (pin "2") (pinfunction "2_2") (pintype "passive"))
      (node (ref "C11") (pin "2") (pinfunction "2_2") (pintype "passive"))
      (node (ref "C12") (pin "2") (pinfunction "2_2") (pintype "passive"))
      (node (ref "C13") (pin "2") (pinfunction "2_2") (pintype "passive"))
      (node (ref "C14") (pin "2") (pinfunction "2_2") (pintype "passive"))
      (node (ref "C15") (pin "2") (pinfunction "2_2") (pintype "passive"))
      (node (ref "C16") (pin "2") (pinfunction "2_2") (pintype "passive"))
      (node (ref "C17") (pin "2") (pinfunction "2_2") (pintype "passive"))
      (node (ref "C18") (pin "2") (pinfunction "2_2") (pintype "passive"))
      (node (ref "C19") (pin "2") (pinfunction "2_2") (pintype "passive"))
      (node (ref "C2") (pin "2") (pinfunction "2_2") (pintype "passive"))
      (node (ref "C20") (pin "2") (pinfunction "2_2") (pintype "passive"))
      (node (ref "C21") (pin "2") (pinfunction "2_2") (pintype "passive"))
      (node (ref "C22") (pin "2") (pinfunction "2_2") (pintype "passive"))
      (node (ref "C23") (pin "2") (pinfunction "2_2") (pintype "passive"))
      (node (ref "C24") (pin "2") (pinfunction "2_2") (pintype "passive"))
      (node (ref "C25") (pin "2") (pinfunction "2_2") (pintype "passive"))
      (node (ref "C26") (pin "2") (pinfunction "2_2") (pintype "passive"))
      (node (ref "C27") (pin "2") (pinfunction "2_2") (pintype "passive"))
      (node (ref "C28") (pin "2") (pinfunction "2_2") (pintype "passive"))
      (node (ref "C29") (pin "2") (pinfunction "2_2") (pintype "passive"))
      (node (ref "C3") (pin "2") (pinfunction "2_2") (pintype "passive"))
      (node (ref "C30") (pin "2") (pinfunction "2_2") (pintype "passive"))
      (node (ref "C31") (pin "2") (pinfunction "2_2") (pintype "passive"))
      (node (ref "C4") (pin "2") (pinfunction "2_2") (pintype "passive"))
      (node (ref "C5") (pin "2") (pinfunction "2_2") (pintype "passive"))
      (node (ref "C6") (pin "2") (pinfunction "2_2") (pintype "passive"))
      (node (ref "C7") (pin "2") (pinfunction "2_2") (pintype "passive"))
      (node (ref "C8") (pin "2") (pinfunction "2_2") (pintype "passive"))
      (node (ref "C9") (pin "2") (pinfunction "2_2") (pintype "passive"))
      (node (ref "D1") (pin "K") (pinfunction "C_K") (pintype "passive"))
      (node (ref "PC0") (pin "3") (pinfunction "GND_3") (pintype "bidirectional"))
      (node (ref "PC0") (pin "4") (pinfunction "GND_4") (pintype "bidirectional"))
      (node (ref "PC0") (pin "62") (pinfunction "GND_62") (pintype "bidirectional"))
      (node (ref "R3") (pin "2") (pinfunction "2_2") (pintype "passive"))
      (node (ref "R4") (pin "2") (pinfunction "2_2") (pintype "passive"))
      (node (ref "U14") (pin "11") (pinfunction "A1_11") (pintype "input"))
      (node (ref "U14") (pin "13") (pinfunction "A2_13") (pintype "input"))
      (node (ref "U14") (pin "15") (pinfunction "A3_15") (pintype "input"))
      (node (ref "U14") (pin "17") (pinfunction "A4_17") (pintype "input"))
      (node (ref "U14") (pin "4") (pinfunction "A2_4") (pintype "input"))
      (node (ref "U14") (pin "6") (pinfunction "A3_6") (pintype "input"))
      (node (ref "U14") (pin "8") (pinfunction "A4_8") (pintype "input"))
      (node (ref "U16") (pin "2") (pinfunction "1D_2") (pintype "input"))
      (node (ref "U16") (pin "3") (pinfunction "2D_3") (pintype "input"))
      (node (ref "U16") (pin "8") (pinfunction "7D_8") (pintype "input"))
      (node (ref "U16") (pin "9") (pinfunction "8D_9") (pintype "input"))
      (node (ref "U23") (pin "5") (pinfunction "EI_5") (pintype "input"))
      (node (ref "U5") (pin "10") (pinfunction "3B_10") (pintype "input"))
      (node (ref "U5") (pin "13") (pinfunction "4B_13") (pintype "input"))
      (node (ref "U5") (pin "3") (pinfunction "1B_3") (pintype "input"))
      (node (ref "U5") (pin "6") (pinfunction "2B_6") (pintype "input"))
      (node (ref "U6") (pin "18") (pinfunction "Q7_18") (pintype "input"))
      (node (ref "U7") (pin "12") (pinfunction "Q4_12") (pintype "input"))
      (node (ref "U7") (pin "14") (pinfunction "Q5_14") (pintype "input"))
      (node (ref "U7") (pin "16") (pinfunction "Q6_16") (pintype "input"))
      (node (ref "U7") (pin "18") (pinfunction "Q7_18") (pintype "input"))
      (node (ref "U7") (pin "5") (pinfunction "Q1_5") (pintype "input"))
      (node (ref "U7") (pin "7") (pinfunction "Q2_7") (pintype "input"))
      (node (ref "U7") (pin "9") (pinfunction "Q3_9") (pintype "input"))
      (node (ref "U8") (pin "19") (pinfunction "G_19") (pintype "input"))
      (node (ref "U9") (pin "12") (pinfunction "D_12") (pintype "input"))
      (node (ref "Y1") (pin "4") (pinfunction "GND_4") (pintype "power_in"))
    )
    (net (code "152") (name "ID0") (class "Default")
      (node (ref "U13") (pin "2") (pinfunction "A1_2") (pintype "input"))
    )
    (net (code "153") (name "ID1") (class "Default")
      (node (ref "U13") (pin "17") (pinfunction "A4_17") (pintype "input"))
    )
    (net (code "154") (name "ID2") (class "Default")
      (node (ref "U13") (pin "4") (pinfunction "A2_4") (pintype "input"))
    )
    (net (code "155") (name "ID3") (class "Default")
      (node (ref "U13") (pin "15") (pinfunction "A3_15") (pintype "input"))
    )
    (net (code "156") (name "ID4") (class "Default")
      (node (ref "U13") (pin "6") (pinfunction "A3_6") (pintype "input"))
    )
    (net (code "157") (name "ID5") (class "Default")
      (node (ref "U13") (pin "13") (pinfunction "A2_13") (pintype "input"))
    )
    (net (code "158") (name "ID6") (class "Default")
      (node (ref "U13") (pin "8") (pinfunction "A4_8") (pintype "input"))
    )
    (net (code "159") (name "ID7") (class "Default")
      (node (ref "U13") (pin "11") (pinfunction "A1_11") (pintype "input"))
    )
    (net (code "160") (name "Net-(D1-PadA)") (class "Default")
      (node (ref "D1") (pin "A") (pinfunction "A_A") (pintype "passive"))
      (node (ref "R1") (pin "1") (pinfunction "1_1") (pintype "passive"))
    )
    (net (code "161") (name "Net-(Q1-B)") (class "Default")
      (node (ref "Q1") (pin "2") (pinfunction "B_2") (pintype "passive"))
      (node (ref "R2") (pin "2") (pinfunction "2_2") (pintype "passive"))
    )
    (net (code "162") (name "Net-(Q1-C)") (class "Default")
      (node (ref "Q1") (pin "3") (pinfunction "C_3") (pintype "passive"))
      (node (ref "R1") (pin "2") (pinfunction "2_2") (pintype "passive"))
    )
    (net (code "163") (name "Net-(U3A-I1)") (class "Default")
      (node (ref "JP2") (pin "2") (pinfunction "2_2") (pintype "passive"))
      (node (ref "U3") (pin "2") (pinfunction "I1_2") (pintype "input"))
    )
    (net (code "164") (name "Net-(U3C-I0)") (class "Default")
      (node (ref "JP3") (pin "1") (pinfunction "1_1") (pintype "passive"))
      (node (ref "R3") (pin "1") (pinfunction "1_1") (pintype "passive"))
      (node (ref "U3") (pin "9") (pinfunction "I0_9") (pintype "input"))
    )
    (net (code "165") (name "Net-(U3C-I1)") (class "Default")
      (node (ref "U3") (pin "10") (pinfunction "I1_10") (pintype "input"))
      (node (ref "U3") (pin "11") (pinfunction "O_11") (pintype "output"))
    )
    (net (code "166") (name "Net-(U3D-I0)") (class "Default")
      (node (ref "U3") (pin "12") (pinfunction "I0_12") (pintype "input"))
      (node (ref "U4") (pin "8") (pinfunction "O_8") (pintype "output"))
    )
    (net (code "167") (name "Net-(U3D-I1)") (class "Default")
      (node (ref "U3") (pin "13") (pinfunction "I1_13") (pintype "input"))
      (node (ref "U7") (pin "19") (pinfunction "P=Q_19") (pintype "output"))
    )
    (net (code "168") (name "Net-(U4A-O)") (class "Default")
      (node (ref "U4") (pin "2") (pinfunction "O_2") (pintype "output"))
      (node (ref "U7") (pin "1") (pinfunction "G_1") (pintype "input"))
    )
    (net (code "169") (name "Net-(U4B-I)") (class "Default")
      (node (ref "U4") (pin "12") (pinfunction "O_12") (pintype "output"))
      (node (ref "U4") (pin "3") (pinfunction "I_3") (pintype "input"))
    )
    (net (code "170") (name "Net-(U4B-O)") (class "Default")
      (node (ref "U4") (pin "4") (pinfunction "O_4") (pintype "output"))
      (node (ref "U9") (pin "3") (pinfunction "CLK_3") (pintype "input"))
    )
    (net (code "171") (name "Net-(U6A-G)") (class "Default")
      (node (ref "JP4") (pin "2") (pinfunction "2_2") (pintype "passive"))
      (node (ref "R4") (pin "1") (pinfunction "1_1") (pintype "passive"))
      (node (ref "U6") (pin "1") (pinfunction "G_1") (pintype "input"))
    )
    (net (code "172") (name "Net-(U10A-Q)") (class "Default")
      (node (ref "U10") (pin "5") (pinfunction "Q_5") (pintype "output"))
      (node (ref "U12") (pin "17") (pinfunction "A4_17") (pintype "input"))
      (node (ref "U29") (pin "2") (pinfunction "1A_2") (pintype "input"))
    )
    (net (code "173") (name "Net-(U10B-CLR)") (class "Default")
      (node (ref "U10") (pin "13") (pinfunction "CLR_13") (pintype "input"))
      (node (ref "U18") (pin "6") (pinfunction "O_6") (pintype "output"))
    )
    (net (code "174") (name "Net-(U11A-Q2)") (class "Default")
      (node (ref "U11") (pin "5") (pinfunction "Q2_5") (pintype "output"))
      (node (ref "U12") (pin "4") (pinfunction "A2_4") (pintype "input"))
      (node (ref "U5") (pin "11") (pinfunction "3A_11") (pintype "input"))
    )
    (net (code "175") (name "Net-(U11A-Q3)") (class "Default")
      (node (ref "U11") (pin "6") (pinfunction "Q3_6") (pintype "output"))
      (node (ref "U12") (pin "13") (pinfunction "A2_13") (pintype "input"))
      (node (ref "U5") (pin "14") (pinfunction "4A_14") (pintype "input"))
    )
    (net (code "176") (name "Net-(U11A-Q4)") (class "Default")
      (node (ref "U11") (pin "9") (pinfunction "Q4_9") (pintype "output"))
      (node (ref "U12") (pin "8") (pinfunction "A4_8") (pintype "input"))
      (node (ref "U4") (pin "1") (pinfunction "I_1") (pintype "input"))
    )
    (net (code "177") (name "Net-(U11A-Q5)") (class "Default")
      (node (ref "U11") (pin "12") (pinfunction "Q5_12") (pintype "output"))
      (node (ref "U12") (pin "11") (pinfunction "A1_11") (pintype "input"))
    )
    (net (code "178") (name "Net-(U11A-Q6)") (class "Default")
      (node (ref "U11") (pin "15") (pinfunction "Q6_15") (pintype "output"))
      (node (ref "U12") (pin "6") (pinfunction "A3_6") (pintype "input"))
    )
    (net (code "179") (name "Net-(U11A-Q7)") (class "Default")
      (node (ref "U11") (pin "16") (pinfunction "Q7_16") (pintype "output"))
      (node (ref "U12") (pin "15") (pinfunction "A3_15") (pintype "input"))
      (node (ref "U5") (pin "5") (pinfunction "2A_5") (pintype "input"))
    )
    (net (code "180") (name "Net-(U11A-Q8)") (class "Default")
      (node (ref "U11") (pin "19") (pinfunction "Q8_19") (pintype "output"))
      (node (ref "U12") (pin "2") (pinfunction "A1_2") (pintype "input"))
      (node (ref "U5") (pin "2") (pinfunction "1A_2") (pintype "input"))
    )
    (net (code "181") (name "Net-(U13A-G)") (class "Default")
      (node (ref "U1") (pin "7") (pinfunction "Y7_7") (pintype "output"))
      (node (ref "U13") (pin "1") (pinfunction "G_1") (pintype "input"))
      (node (ref "U13") (pin "19") (pinfunction "G_19") (pintype "input"))
    )
    (net (code "182") (name "Net-(U14A-G)") (class "Default")
      (node (ref "U14") (pin "1") (pinfunction "G_1") (pintype "input"))
      (node (ref "U14") (pin "19") (pinfunction "G_19") (pintype "input"))
      (node (ref "U22") (pin "7") (pinfunction "Y7_7") (pintype "output"))
    )
    (net (code "183") (name "Net-(U15A-B1)") (class "Default")
      (node (ref "U15") (pin "18") (pinfunction "B1_18") (pintype "bidirectional"))
      (node (ref "U20") (pin "33") (pinfunction "D0_33") (pintype "bidirectional"))
    )
    (net (code "184") (name "Net-(U15A-B2)") (class "Default")
      (node (ref "U15") (pin "17") (pinfunction "B2_17") (pintype "bidirectional"))
      (node (ref "U20") (pin "32") (pinfunction "D1_32") (pintype "bidirectional"))
    )
    (net (code "185") (name "Net-(U15A-B3)") (class "Default")
      (node (ref "U15") (pin "16") (pinfunction "B3_16") (pintype "bidirectional"))
      (node (ref "U20") (pin "31") (pinfunction "D2_31") (pintype "bidirectional"))
    )
    (net (code "186") (name "Net-(U15A-B4)") (class "Default")
      (node (ref "U15") (pin "15") (pinfunction "B4_15") (pintype "bidirectional"))
      (node (ref "U20") (pin "30") (pinfunction "D3_30") (pintype "bidirectional"))
    )
    (net (code "187") (name "Net-(U15A-B5)") (class "Default")
      (node (ref "U15") (pin "14") (pinfunction "B5_14") (pintype "bidirectional"))
      (node (ref "U20") (pin "29") (pinfunction "D4_29") (pintype "bidirectional"))
    )
    (net (code "188") (name "Net-(U15A-B6)") (class "Default")
      (node (ref "U15") (pin "13") (pinfunction "B6_13") (pintype "bidirectional"))
      (node (ref "U20") (pin "28") (pinfunction "D5_28") (pintype "bidirectional"))
    )
    (net (code "189") (name "Net-(U15A-B7)") (class "Default")
      (node (ref "U15") (pin "12") (pinfunction "B7_12") (pintype "bidirectional"))
      (node (ref "U20") (pin "27") (pinfunction "D6_27") (pintype "bidirectional"))
    )
    (net (code "190") (name "Net-(U15A-B8)") (class "Default")
      (node (ref "U15") (pin "11") (pinfunction "B8_11") (pintype "bidirectional"))
      (node (ref "U20") (pin "26") (pinfunction "D7_26") (pintype "bidirectional"))
    )
    (net (code "191") (name "Net-(U15A-DIR)") (class "Default")
      (node (ref "U15") (pin "1") (pinfunction "DIR_1") (pintype "input"))
      (node (ref "U17") (pin "1") (pinfunction "I0_1") (pintype "input"))
      (node (ref "U19") (pin "3") (pinfunction "I_3") (pintype "input"))
      (node (ref "U20") (pin "34") (pinfunction "R~{WB}_34") (pintype "output"))
    )
    (net (code "192") (name "Net-(U16A-3D)") (class "Default")
      (node (ref "U16") (pin "4") (pinfunction "3D_4") (pintype "input"))
      (node (ref "U23") (pin "9") (pinfunction "A0_9") (pintype "output"))
    )
    (net (code "193") (name "Net-(U16A-4D)") (class "Default")
      (node (ref "U16") (pin "5") (pinfunction "4D_5") (pintype "input"))
      (node (ref "U23") (pin "7") (pinfunction "A1_7") (pintype "output"))
    )
    (net (code "194") (name "Net-(U16A-5D)") (class "Default")
      (node (ref "U16") (pin "6") (pinfunction "5D_6") (pintype "input"))
      (node (ref "U23") (pin "6") (pinfunction "A2_6") (pintype "output"))
    )
    (net (code "195") (name "Net-(U16A-6D)") (class "Default")
      (node (ref "U16") (pin "7") (pinfunction "6D_7") (pintype "input"))
      (node (ref "U19") (pin "10") (pinfunction "O_10") (pintype "output"))
    )
    (net (code "196") (name "Net-(U17A-I1)") (class "Default")
      (node (ref "JP1") (pin "2") (pinfunction "2_2") (pintype "passive"))
      (node (ref "U17") (pin "2") (pinfunction "I1_2") (pintype "input"))
      (node (ref "U17") (pin "4") (pinfunction "I0_4") (pintype "input"))
      (node (ref "U20") (pin "37") (pinfunction "PHI2_37") (pintype "input"))
      (node (ref "U8") (pin "17") (pinfunction "A4_17") (pintype "input"))
    )
    (net (code "197") (name "Net-(U17B-I1)") (class "Default")
      (node (ref "U17") (pin "5") (pinfunction "I1_5") (pintype "input"))
      (node (ref "U19") (pin "4") (pinfunction "O_4") (pintype "output"))
    )
    (net (code "198") (name "Net-(U17C-I0)") (class "Default")
      (node (ref "R7") (pin "2") (pinfunction "2_2") (pintype "passive"))
      (node (ref "U17") (pin "9") (pinfunction "I0_9") (pintype "input"))
      (node (ref "U19") (pin "2") (pinfunction "O_2") (pintype "output"))
    )
    (net (code "199") (name "Net-(U17C-I1)") (class "Default")
      (node (ref "U17") (pin "10") (pinfunction "I1_10") (pintype "input"))
      (node (ref "U19") (pin "12") (pinfunction "O_12") (pintype "output"))
    )
    (net (code "200") (name "Net-(U17D-I0)") (class "Default")
      (node (ref "U17") (pin "12") (pinfunction "I0_12") (pintype "input"))
      (node (ref "U18") (pin "11") (pinfunction "O_11") (pintype "output"))
    )
    (net (code "201") (name "Net-(U17D-I1)") (class "Default")
      (node (ref "U17") (pin "13") (pinfunction "I1_13") (pintype "input"))
      (node (ref "U19") (pin "6") (pinfunction "O_6") (pintype "output"))
    )
    (net (code "202") (name "Net-(U18A-I0)") (class "Default")
      (node (ref "U18") (pin "1") (pinfunction "I0_1") (pintype "input"))
      (node (ref "U4") (pin "10") (pinfunction "O_10") (pintype "output"))
    )
    (net (code "203") (name "Net-(U18A-O)") (class "Default")
      (node (ref "U18") (pin "3") (pinfunction "O_3") (pintype "output"))
      (node (ref "U9") (pin "2") (pinfunction "D_2") (pintype "input"))
    )
    (net (code "204") (name "Net-(U18C-O)") (class "Default")
      (node (ref "U18") (pin "8") (pinfunction "O_8") (pintype "output"))
      (node (ref "U20") (pin "4") (pinfunction "~{IRQB}_4") (pintype "input"))
    )
    (net (code "205") (name "Net-(U19A-I)") (class "Default")
      (node (ref "U19") (pin "1") (pinfunction "I_1") (pintype "input"))
      (node (ref "U3") (pin "6") (pinfunction "O_6") (pintype "output"))
    )
    (net (code "206") (name "Net-(U19D-I)") (class "Default")
      (node (ref "U19") (pin "9") (pinfunction "I_9") (pintype "input"))
      (node (ref "U20") (pin "7") (pinfunction "SYNC_7") (pintype "output"))
    )
    (net (code "207") (name "Net-(U19D-O)") (class "Default")
      (node (ref "U19") (pin "8") (pinfunction "O_8") (pintype "output"))
      (node (ref "U8") (pin "6") (pinfunction "A3_6") (pintype "input"))
    )
    (net (code "208") (name "Net-(U19E-I)") (class "Default")
      (node (ref "U19") (pin "11") (pinfunction "I_11") (pintype "input"))
      (node (ref "U23") (pin "15") (pinfunction "EO_15") (pintype "output"))
    )
    (net (code "209") (name "Net-(U20A-~{NMIB})") (class "Default")
      (node (ref "JP5") (pin "2") (pinfunction "2_2") (pintype "passive"))
      (node (ref "R6") (pin "1") (pinfunction "1_1") (pintype "passive"))
      (node (ref "U20") (pin "6") (pinfunction "~{NMIB}_6") (pintype "input"))
    )
    (net (code "210") (name "Net-(U21A-A1)") (class "Default")
      (node (ref "U21") (pin "2") (pinfunction "A1_2") (pintype "input"))
      (node (ref "U26") (pin "19") (pinfunction "Q8_19") (pintype "output"))
      (node (ref "U27") (pin "1") (pinfunction "I0_1") (pintype "input"))
    )
    (net (code "211") (name "Net-(U21A-A2)") (class "Default")
      (node (ref "U21") (pin "4") (pinfunction "A2_4") (pintype "input"))
      (node (ref "U26") (pin "16") (pinfunction "Q7_16") (pintype "output"))
      (node (ref "U27") (pin "4") (pinfunction "I0_4") (pintype "input"))
    )
    (net (code "212") (name "Net-(U21A-A3)") (class "Default")
      (node (ref "U21") (pin "6") (pinfunction "A3_6") (pintype "input"))
      (node (ref "U26") (pin "15") (pinfunction "Q6_15") (pintype "output"))
      (node (ref "U27") (pin "12") (pinfunction "I0_12") (pintype "input"))
    )
    (net (code "213") (name "Net-(U21A-A4)") (class "Default")
      (node (ref "U21") (pin "8") (pinfunction "A4_8") (pintype "input"))
      (node (ref "U26") (pin "12") (pinfunction "Q5_12") (pintype "output"))
      (node (ref "U27") (pin "9") (pinfunction "I0_9") (pintype "input"))
    )
    (net (code "214") (name "Net-(U21B-A1)") (class "Default")
      (node (ref "U21") (pin "11") (pinfunction "A1_11") (pintype "input"))
      (node (ref "U26") (pin "9") (pinfunction "Q4_9") (pintype "output"))
      (node (ref "U28") (pin "4") (pinfunction "I0_4") (pintype "input"))
    )
    (net (code "215") (name "Net-(U21B-A2)") (class "Default")
      (node (ref "U21") (pin "13") (pinfunction "A2_13") (pintype "input"))
      (node (ref "U26") (pin "6") (pinfunction "Q3_6") (pintype "output"))
      (node (ref "U28") (pin "1") (pinfunction "I0_1") (pintype "input"))
    )
    (net (code "216") (name "Net-(U21B-A3)") (class "Default")
      (node (ref "U21") (pin "15") (pinfunction "A3_15") (pintype "input"))
      (node (ref "U26") (pin "5") (pinfunction "Q2_5") (pintype "output"))
      (node (ref "U28") (pin "12") (pinfunction "I0_12") (pintype "input"))
    )
    (net (code "217") (name "Net-(U21B-A4)") (class "Default")
      (node (ref "U21") (pin "17") (pinfunction "A4_17") (pintype "input"))
      (node (ref "U26") (pin "2") (pinfunction "Q1_2") (pintype "output"))
      (node (ref "U28") (pin "9") (pinfunction "I0_9") (pintype "input"))
    )
    (net (code "218") (name "Net-(U23A-0)") (class "Default")
      (node (ref "U23") (pin "10") (pinfunction "0_10") (pintype "input"))
      (node (ref "U28") (pin "8") (pinfunction "O_8") (pintype "output"))
    )
    (net (code "219") (name "Net-(U23A-1)") (class "Default")
      (node (ref "U23") (pin "11") (pinfunction "1_11") (pintype "input"))
      (node (ref "U28") (pin "11") (pinfunction "O_11") (pintype "output"))
    )
    (net (code "220") (name "Net-(U23A-2)") (class "Default")
      (node (ref "U23") (pin "12") (pinfunction "2_12") (pintype "input"))
      (node (ref "U28") (pin "3") (pinfunction "O_3") (pintype "output"))
    )
    (net (code "221") (name "Net-(U23A-3)") (class "Default")
      (node (ref "U23") (pin "13") (pinfunction "3_13") (pintype "input"))
      (node (ref "U28") (pin "6") (pinfunction "O_6") (pintype "output"))
    )
    (net (code "222") (name "Net-(U23A-4)") (class "Default")
      (node (ref "U23") (pin "1") (pinfunction "4_1") (pintype "input"))
      (node (ref "U27") (pin "8") (pinfunction "O_8") (pintype "output"))
    )
    (net (code "223") (name "Net-(U23A-5)") (class "Default")
      (node (ref "U23") (pin "2") (pinfunction "5_2") (pintype "input"))
      (node (ref "U27") (pin "11") (pinfunction "O_11") (pintype "output"))
    )
    (net (code "224") (name "Net-(U23A-6)") (class "Default")
      (node (ref "U23") (pin "3") (pinfunction "6_3") (pintype "input"))
      (node (ref "U27") (pin "6") (pinfunction "O_6") (pintype "output"))
    )
    (net (code "225") (name "Net-(U23A-7)") (class "Default")
      (node (ref "U23") (pin "4") (pinfunction "7_4") (pintype "input"))
      (node (ref "U27") (pin "3") (pinfunction "O_3") (pintype "output"))
    )
    (net (code "226") (name "Net-(U29A-~{A}{slash}B)") (class "Default")
      (node (ref "U29") (pin "1") (pinfunction "~{A}/B_1") (pintype "input"))
      (node (ref "U3") (pin "8") (pinfunction "O_8") (pintype "output"))
      (node (ref "U5") (pin "1") (pinfunction "~{A}/B_1") (pintype "input"))
    )
    (net (code "227") (name "Net-(U30A-CLK)") (class "Default")
      (node (ref "JP1") (pin "3") (pinfunction "3_3") (pintype "passive"))
      (node (ref "U30") (pin "11") (pinfunction "CLK_11") (pintype "input"))
      (node (ref "U30") (pin "3") (pinfunction "CLK_3") (pintype "input"))
      (node (ref "Y1") (pin "5") (pinfunction "FO_5") (pintype "output"))
    )
    (net (code "228") (name "Net-(U30A-D)") (class "Default")
      (node (ref "U3") (pin "3") (pinfunction "O_3") (pintype "output"))
      (node (ref "U30") (pin "2") (pinfunction "D_2") (pintype "input"))
    )
    (net (code "229") (name "Net-(U30A-Q)") (class "Default")
      (node (ref "JP1") (pin "1") (pinfunction "1_1") (pintype "passive"))
      (node (ref "U3") (pin "1") (pinfunction "I0_1") (pintype "input"))
      (node (ref "U30") (pin "12") (pinfunction "D_12") (pintype "input"))
      (node (ref "U30") (pin "5") (pinfunction "Q_5") (pintype "output"))
    )
    (net (code "230") (name "Net-(U30B-Q)") (class "Default")
      (node (ref "JP2") (pin "3") (pinfunction "3_3") (pintype "passive"))
      (node (ref "U30") (pin "9") (pinfunction "Q_9") (pintype "output"))
    )
    (net (code "231") (name "Net-(Y1-OE)") (class "Default")
      (node (ref "R5") (pin "1") (pinfunction "1_1") (pintype "passive"))
      (node (ref "Y1") (pin "1") (pinfunction "OE_1") (pintype "input"))
    )
    (net (code "232") (name "PH1") (class "Default")
      (node (ref "U16") (pin "11") (pinfunction "CLK_11") (pintype "input"))
      (node (ref "U20") (pin "3") (pinfunction "PHI1O_3") (pintype "output"))
      (node (ref "U9") (pin "11") (pinfunction "CLK_11") (pintype "input"))
    )
    (net (code "233") (name "PH2") (class "Default")
      (node (ref "U20") (pin "39") (pinfunction "PHI2O_39") (pintype "output"))
      (node (ref "U4") (pin "13") (pinfunction "I_13") (pintype "input"))
    )
    (net (code "234") (name "RDY") (class "Default")
      (node (ref "R7") (pin "1") (pinfunction "1_1") (pintype "passive"))
      (node (ref "U19") (pin "13") (pinfunction "I_13") (pintype "input"))
      (node (ref "U20") (pin "2") (pinfunction "RDY_2") (pintype "bidirectional"))
    )
    (net (code "235") (name "VCC") (class "Default")
      (node (ref "C1") (pin "1") (pinfunction "1_1") (pintype "passive"))
      (node (ref "C10") (pin "1") (pinfunction "1_1") (pintype "passive"))
      (node (ref "C11") (pin "1") (pinfunction "1_1") (pintype "passive"))
      (node (ref "C12") (pin "1") (pinfunction "1_1") (pintype "passive"))
      (node (ref "C13") (pin "1") (pinfunction "1_1") (pintype "passive"))
      (node (ref "C14") (pin "1") (pinfunction "1_1") (pintype "passive"))
      (node (ref "C15") (pin "1") (pinfunction "1_1") (pintype "passive"))
      (node (ref "C16") (pin "1") (pinfunction "1_1") (pintype "passive"))
      (node (ref "C17") (pin "1") (pinfunction "1_1") (pintype "passive"))
      (node (ref "C18") (pin "1") (pinfunction "1_1") (pintype "passive"))
      (node (ref "C19") (pin "1") (pinfunction "1_1") (pintype "passive"))
      (node (ref "C2") (pin "1") (pinfunction "1_1") (pintype "passive"))
      (node (ref "C20") (pin "1") (pinfunction "1_1") (pintype "passive"))
      (node (ref "C21") (pin "1") (pinfunction "1_1") (pintype "passive"))
      (node (ref "C22") (pin "1") (pinfunction "1_1") (pintype "passive"))
      (node (ref "C23") (pin "1") (pinfunction "1_1") (pintype "passive"))
      (node (ref "C24") (pin "1") (pinfunction "1_1") (pintype "passive"))
      (node (ref "C25") (pin "1") (pinfunction "1_1") (pintype "passive"))
      (node (ref "C26") (pin "1") (pinfunction "1_1") (pintype "passive"))
      (node (ref "C27") (pin "1") (pinfunction "1_1") (pintype "passive"))
      (node (ref "C28") (pin "1") (pinfunction "1_1") (pintype "passive"))
      (node (ref "C29") (pin "1") (pinfunction "1_1") (pintype "passive"))
      (node (ref "C3") (pin "1") (pinfunction "1_1") (pintype "passive"))
      (node (ref "C30") (pin "1") (pinfunction "1_1") (pintype "passive"))
      (node (ref "C31") (pin "1") (pinfunction "1_1") (pintype "passive"))
      (node (ref "C4") (pin "1") (pinfunction "1_1") (pintype "passive"))
      (node (ref "C5") (pin "1") (pinfunction "1_1") (pintype "passive"))
      (node (ref "C6") (pin "1") (pinfunction "1_1") (pintype "passive"))
      (node (ref "C7") (pin "1") (pinfunction "1_1") (pintype "passive"))
      (node (ref "C8") (pin "1") (pinfunction "1_1") (pintype "passive"))
      (node (ref "C9") (pin "1") (pinfunction "1_1") (pintype "passive"))
      (node (ref "JP2") (pin "1") (pinfunction "1_1") (pintype "passive"))
      (node (ref "JP4") (pin "1") (pinfunction "1_1") (pintype "passive"))
      (node (ref "PC0") (pin "5") (pinfunction "+5V_5") (pintype "bidirectional"))
      (node (ref "PC0") (pin "6") (pinfunction "+5V_6") (pintype "bidirectional"))
      (node (ref "Q1") (pin "1") (pinfunction "E_1") (pintype "passive"))
      (node (ref "R5") (pin "2") (pinfunction "2_2") (pintype "passive"))
      (node (ref "R6") (pin "2") (pinfunction "2_2") (pintype "passive"))
      (node (ref "U10") (pin "1") (pinfunction "CLR_1") (pintype "input"))
      (node (ref "U10") (pin "11") (pinfunction "CLK_11") (pintype "input"))
      (node (ref "U10") (pin "12") (pinfunction "D_12") (pintype "input"))
      (node (ref "U11") (pin "3") (pinfunction "D1_3") (pintype "input"))
      (node (ref "U14") (pin "2") (pinfunction "A1_2") (pintype "input"))
      (node (ref "U2") (pin "6") (pinfunction "G1_6") (pintype "input"))
      (node (ref "U20") (pin "36") (pinfunction "BE_36") (pintype "input"))
      (node (ref "U20") (pin "38") (pinfunction "~{SOB}_38") (pintype "input"))
      (node (ref "U22") (pin "6") (pinfunction "G1_6") (pintype "input"))
      (node (ref "U29") (pin "10") (pinfunction "3B_10") (pintype "input"))
      (node (ref "U29") (pin "11") (pinfunction "3A_11") (pintype "input"))
      (node (ref "U29") (pin "13") (pinfunction "4B_13") (pintype "input"))
      (node (ref "U29") (pin "14") (pinfunction "4A_14") (pintype "input"))
      (node (ref "U29") (pin "5") (pinfunction "2A_5") (pintype "input"))
      (node (ref "U29") (pin "6") (pinfunction "2B_6") (pintype "input"))
      (node (ref "U30") (pin "1") (pinfunction "CLR_1") (pintype "input"))
      (node (ref "U30") (pin "10") (pinfunction "PRE_10") (pintype "input"))
      (node (ref "U30") (pin "13") (pinfunction "CLR_13") (pintype "input"))
      (node (ref "U30") (pin "4") (pinfunction "PRE_4") (pintype "input"))
      (node (ref "U4") (pin "5") (pinfunction "I_5") (pintype "input"))
      (node (ref "U6") (pin "12") (pinfunction "Q4_12") (pintype "input"))
      (node (ref "U6") (pin "14") (pinfunction "Q5_14") (pintype "input"))
      (node (ref "U6") (pin "16") (pinfunction "Q6_16") (pintype "input"))
      (node (ref "U6") (pin "2") (pinfunction "P0_2") (pintype "input"))
      (node (ref "U6") (pin "3") (pinfunction "Q0_3") (pintype "input"))
      (node (ref "U6") (pin "4") (pinfunction "P1_4") (pintype "input"))
      (node (ref "U6") (pin "5") (pinfunction "Q1_5") (pintype "input"))
      (node (ref "U6") (pin "6") (pinfunction "P2_6") (pintype "input"))
      (node (ref "U6") (pin "7") (pinfunction "Q2_7") (pintype "input"))
      (node (ref "U6") (pin "8") (pinfunction "P3_8") (pintype "input"))
      (node (ref "U6") (pin "9") (pinfunction "Q3_9") (pintype "input"))
      (node (ref "U7") (pin "2") (pinfunction "P0_2") (pintype "input"))
      (node (ref "U7") (pin "3") (pinfunction "Q0_3") (pintype "input"))
      (node (ref "U8") (pin "8") (pinfunction "A4_8") (pintype "input"))
      (node (ref "U9") (pin "4") (pinfunction "PRE_4") (pintype "input"))
      (node (ref "Y1") (pin "8") (pinfunction "VCC_8") (pintype "power_in"))
    )
    (net (code "236") (name "unconnected-(PC0-+3.3V-Pad2)") (class "Default")
      (node (ref "PC0") (pin "2") (pinfunction "+3.3V_2") (pintype "bidirectional"))
    )
    (net (code "237") (name "unconnected-(PC0-+5VSB-Pad8)") (class "Default")
      (node (ref "PC0") (pin "8") (pinfunction "+5VSB_8") (pintype "bidirectional"))
    )
    (net (code "238") (name "unconnected-(PC0-+12V-Pad1)") (class "Default")
      (node (ref "PC0") (pin "1") (pinfunction "+12V_1") (pintype "bidirectional"))
    )
    (net (code "239") (name "unconnected-(PC0--12V-Pad7)") (class "Default")
      (node (ref "PC0") (pin "7") (pinfunction "-12V_7") (pintype "bidirectional"))
    )
    (net (code "240") (name "unconnected-(PC0-~{BUSRQ}-Pad10)") (class "Default")
      (node (ref "PC0") (pin "10") (pinfunction "~{BUSRQ}_10") (pintype "bidirectional"))
    )
    (net (code "241") (name "unconnected-(PC0-~{CINH}-Pad13)") (class "Default")
      (node (ref "PC0") (pin "13") (pinfunction "~{CINH}_13") (pintype "bidirectional"))
    )
    (net (code "242") (name "unconnected-(U1A-Y0-Pad15)") (class "Default")
      (node (ref "U1") (pin "15") (pinfunction "Y0_15") (pintype "output"))
    )
    (net (code "243") (name "unconnected-(U1A-Y1-Pad14)") (class "Default")
      (node (ref "U1") (pin "14") (pinfunction "Y1_14") (pintype "output"))
    )
    (net (code "244") (name "unconnected-(U1A-Y2-Pad13)") (class "Default")
      (node (ref "U1") (pin "13") (pinfunction "Y2_13") (pintype "output"))
    )
    (net (code "245") (name "unconnected-(U1A-Y3-Pad12)") (class "Default")
      (node (ref "U1") (pin "12") (pinfunction "Y3_12") (pintype "output"))
    )
    (net (code "246") (name "unconnected-(U1A-Y4-Pad11)") (class "Default")
      (node (ref "U1") (pin "11") (pinfunction "Y4_11") (pintype "output"))
    )
    (net (code "247") (name "unconnected-(U1A-Y5-Pad10)") (class "Default")
      (node (ref "U1") (pin "10") (pinfunction "Y5_10") (pintype "output"))
    )
    (net (code "248") (name "unconnected-(U1A-Y6-Pad9)") (class "Default")
      (node (ref "U1") (pin "9") (pinfunction "Y6_9") (pintype "output"))
    )
    (net (code "249") (name "unconnected-(U2A-Y0-Pad15)") (class "Default")
      (node (ref "U2") (pin "15") (pinfunction "Y0_15") (pintype "output"))
    )
    (net (code "250") (name "unconnected-(U2A-Y1-Pad14)") (class "Default")
      (node (ref "U2") (pin "14") (pinfunction "Y1_14") (pintype "output"))
    )
    (net (code "251") (name "unconnected-(U2A-Y6-Pad9)") (class "Default")
      (node (ref "U2") (pin "9") (pinfunction "Y6_9") (pintype "output"))
    )
    (net (code "252") (name "unconnected-(U2A-Y7-Pad7)") (class "Default")
      (node (ref "U2") (pin "7") (pinfunction "Y7_7") (pintype "output"))
    )
    (net (code "253") (name "unconnected-(U4C-O-Pad6)") (class "Default")
      (node (ref "U4") (pin "6") (pinfunction "O_6") (pintype "output"))
    )
    (net (code "254") (name "unconnected-(U8A-Y4-Pad12)") (class "Default")
      (node (ref "U8") (pin "12") (pinfunction "Y4_12") (pintype "tri_state"))
    )
    (net (code "255") (name "unconnected-(U9B-Q-Pad9)") (class "Default")
      (node (ref "U9") (pin "9") (pinfunction "Q_9") (pintype "output"))
    )
    (net (code "256") (name "unconnected-(U10A-~{Q}-Pad6)") (class "Default")
      (node (ref "U10") (pin "6") (pinfunction "~{Q}_6") (pintype "output"))
    )
    (net (code "257") (name "unconnected-(U10B-Q-Pad9)") (class "Default")
      (node (ref "U10") (pin "9") (pinfunction "Q_9") (pintype "output"))
    )
    (net (code "258") (name "unconnected-(U11A-Q1-Pad2)") (class "Default")
      (node (ref "U11") (pin "2") (pinfunction "Q1_2") (pintype "output"))
    )
    (net (code "259") (name "unconnected-(U22A-Y0-Pad15)") (class "Default")
      (node (ref "U22") (pin "15") (pinfunction "Y0_15") (pintype "output"))
    )
    (net (code "260") (name "unconnected-(U22A-Y1-Pad14)") (class "Default")
      (node (ref "U22") (pin "14") (pinfunction "Y1_14") (pintype "output"))
    )
    (net (code "261") (name "unconnected-(U22A-Y2-Pad13)") (class "Default")
      (node (ref "U22") (pin "13") (pinfunction "Y2_13") (pintype "output"))
    )
    (net (code "262") (name "unconnected-(U22A-Y3-Pad12)") (class "Default")
      (node (ref "U22") (pin "12") (pinfunction "Y3_12") (pintype "output"))
    )
    (net (code "263") (name "unconnected-(U22A-Y4-Pad11)") (class "Default")
      (node (ref "U22") (pin "11") (pinfunction "Y4_11") (pintype "output"))
    )
    (net (code "264") (name "unconnected-(U22A-Y5-Pad10)") (class "Default")
      (node (ref "U22") (pin "10") (pinfunction "Y5_10") (pintype "output"))
    )
    (net (code "265") (name "unconnected-(U29A-2Y-Pad7)") (class "Default")
      (node (ref "U29") (pin "7") (pinfunction "2Y_7") (pintype "tri_state"))
    )
    (net (code "266") (name "unconnected-(U29A-3Y-Pad9)") (class "Default")
      (node (ref "U29") (pin "9") (pinfunction "3Y_9") (pintype "tri_state"))
    )
    (net (code "267") (name "unconnected-(U29A-4Y-Pad12)") (class "Default")
      (node (ref "U29") (pin "12") (pinfunction "4Y_12") (pintype "tri_state"))
    )
    (net (code "268") (name "unconnected-(U30A-~{Q}-Pad6)") (class "Default")
      (node (ref "U30") (pin "6") (pinfunction "~{Q}_6") (pintype "output"))
    )
    (net (code "269") (name "unconnected-(U30B-~{Q}-Pad8)") (class "Default")
      (node (ref "U30") (pin "8") (pinfunction "~{Q}_8") (pintype "output"))
    )
    (net (code "270") (name "~{BBUSACK}") (class "Default")
      (node (ref "PC0") (pin "20") (pinfunction "~{BUSACK}_20") (pintype "bidirectional"))
      (node (ref "U8") (pin "7") (pinfunction "Y2_7") (pintype "tri_state"))
    )
    (net (code "271") (name "~{BCBR}") (class "Default")
      (node (ref "PC0") (pin "12") (pinfunction "~{CBR}_12") (pintype "bidirectional"))
      (node (ref "U4") (pin "11") (pinfunction "I_11") (pintype "input"))
    )
    (net (code "272") (name "~{BCSX}") (class "Default")
      (node (ref "PC0") (pin "9") (pinfunction "~{CSX}_9") (pintype "bidirectional"))
      (node (ref "U1") (pin "4") (pinfunction "G2A_4") (pintype "input"))
      (node (ref "U2") (pin "5") (pinfunction "G2B_5") (pintype "input"))
    )
    (net (code "273") (name "~{BFETCH}") (class "Default")
      (node (ref "PC0") (pin "19") (pinfunction "~{FETCH}_19") (pintype "bidirectional"))
      (node (ref "U8") (pin "14") (pinfunction "Y3_14") (pintype "tri_state"))
    )
    (net (code "274") (name "~{BHALT}") (class "Default")
      (node (ref "PC0") (pin "17") (pinfunction "~{HALT}_17") (pintype "bidirectional"))
      (node (ref "U8") (pin "5") (pinfunction "Y3_5") (pintype "tri_state"))
    )
    (net (code "275") (name "~{BINH}") (class "Default")
      (node (ref "PC0") (pin "11") (pinfunction "~{INH}_11") (pintype "bidirectional"))
      (node (ref "U17") (pin "11") (pinfunction "O_11") (pintype "output"))
    )
    (net (code "276") (name "~{BINT}") (class "Default")
      (node (ref "PC0") (pin "51") (pinfunction "~{INT}_51") (pintype "bidirectional"))
      (node (ref "U18") (pin "10") (pinfunction "I1_10") (pintype "input"))
    )
    (net (code "277") (name "~{BIOSEL}") (class "Default")
      (node (ref "PC0") (pin "16") (pinfunction "~{IO}_16") (pintype "bidirectional"))
      (node (ref "U25") (pin "18") (pinfunction "Y1_18") (pintype "tri_state"))
    )
    (net (code "278") (name "~{BIRQ0}") (class "Default")
      (node (ref "PC0") (pin "53") (pinfunction "~{IRQ0}_53") (pintype "bidirectional"))
      (node (ref "U27") (pin "2") (pinfunction "I1_2") (pintype "input"))
    )
    (net (code "279") (name "~{BIRQ1}") (class "Default")
      (node (ref "PC0") (pin "54") (pinfunction "~{IRQ1}_54") (pintype "bidirectional"))
      (node (ref "U27") (pin "5") (pinfunction "I1_5") (pintype "input"))
    )
    (net (code "280") (name "~{BIRQ2}") (class "Default")
      (node (ref "PC0") (pin "55") (pinfunction "~{IRQ2}_55") (pintype "bidirectional"))
      (node (ref "U27") (pin "13") (pinfunction "I1_13") (pintype "input"))
    )
    (net (code "281") (name "~{BIRQ3}") (class "Default")
      (node (ref "PC0") (pin "56") (pinfunction "~{IRQ3}_56") (pintype "bidirectional"))
      (node (ref "U27") (pin "10") (pinfunction "I1_10") (pintype "input"))
    )
    (net (code "282") (name "~{BIRQ4}") (class "Default")
      (node (ref "PC0") (pin "57") (pinfunction "~{IRQ4}_57") (pintype "bidirectional"))
      (node (ref "U28") (pin "5") (pinfunction "I1_5") (pintype "input"))
    )
    (net (code "283") (name "~{BIRQ5}") (class "Default")
      (node (ref "PC0") (pin "58") (pinfunction "~{IRQ5}_58") (pintype "bidirectional"))
      (node (ref "U28") (pin "2") (pinfunction "I1_2") (pintype "input"))
    )
    (net (code "284") (name "~{BIRQ6}") (class "Default")
      (node (ref "PC0") (pin "59") (pinfunction "~{IRQ6}_59") (pintype "bidirectional"))
      (node (ref "U28") (pin "13") (pinfunction "I1_13") (pintype "input"))
    )
    (net (code "285") (name "~{BIRQ7}") (class "Default")
      (node (ref "PC0") (pin "60") (pinfunction "~{IRQ7}_60") (pintype "bidirectional"))
      (node (ref "U28") (pin "10") (pinfunction "I1_10") (pintype "input"))
    )
    (net (code "286") (name "~{BIRQX}") (class "Default")
      (node (ref "PC0") (pin "52") (pinfunction "~{IRQX}_52") (pintype "bidirectional"))
      (node (ref "U10") (pin "8") (pinfunction "~{Q}_8") (pintype "output"))
    )
    (net (code "287") (name "~{BNMI}") (class "Default")
      (node (ref "JP5") (pin "1") (pinfunction "1_1") (pintype "passive"))
      (node (ref "PC0") (pin "61") (pinfunction "~{NMI}_61") (pintype "bidirectional"))
    )
    (net (code "288") (name "~{BRD}") (class "Default")
      (node (ref "PC0") (pin "21") (pinfunction "~{RD}_21") (pintype "bidirectional"))
      (node (ref "U1") (pin "5") (pinfunction "G2B_5") (pintype "input"))
      (node (ref "U2") (pin "2") (pinfunction "B_2") (pintype "input"))
      (node (ref "U8") (pin "18") (pinfunction "Y1_18") (pintype "tri_state"))
    )
    (net (code "289") (name "~{BRST}") (class "Default")
      (node (ref "PC0") (pin "14") (pinfunction "~{RST}_14") (pintype "bidirectional"))
      (node (ref "U8") (pin "11") (pinfunction "A1_11") (pintype "input"))
    )
    (net (code "290") (name "~{BUSACK}") (class "Default")
      (node (ref "U10") (pin "10") (pinfunction "PRE_10") (pintype "input"))
      (node (ref "U8") (pin "13") (pinfunction "A2_13") (pintype "input"))
      (node (ref "U9") (pin "10") (pinfunction "PRE_10") (pintype "input"))
      (node (ref "U9") (pin "6") (pinfunction "~{Q}_6") (pintype "output"))
    )
    (net (code "291") (name "~{BWAIT}") (class "Default")
      (node (ref "PC0") (pin "18") (pinfunction "~{WAIT}_18") (pintype "bidirectional"))
      (node (ref "U3") (pin "4") (pinfunction "I0_4") (pintype "input"))
    )
    (net (code "292") (name "~{BWR}") (class "Default")
      (node (ref "PC0") (pin "22") (pinfunction "~{WR}_22") (pintype "bidirectional"))
      (node (ref "U2") (pin "3") (pinfunction "C_3") (pintype "input"))
      (node (ref "U8") (pin "16") (pinfunction "Y2_16") (pintype "tri_state"))
    )
    (net (code "293") (name "~{CS0_READ}") (class "Default")
      (node (ref "U12") (pin "1") (pinfunction "G_1") (pintype "input"))
      (node (ref "U12") (pin "19") (pinfunction "G_19") (pintype "input"))
      (node (ref "U2") (pin "11") (pinfunction "Y4_11") (pintype "output"))
    )
    (net (code "294") (name "~{CS0_WRITE}") (class "Default")
      (node (ref "U10") (pin "3") (pinfunction "CLK_3") (pintype "input"))
      (node (ref "U11") (pin "11") (pinfunction "CLK_11") (pintype "input"))
      (node (ref "U2") (pin "13") (pinfunction "Y2_13") (pintype "output"))
    )
    (net (code "295") (name "~{CS1_READ}") (class "Default")
      (node (ref "U2") (pin "10") (pinfunction "Y5_10") (pintype "output"))
      (node (ref "U21") (pin "1") (pinfunction "G_1") (pintype "input"))
      (node (ref "U21") (pin "19") (pinfunction "G_19") (pintype "input"))
    )
    (net (code "296") (name "~{CS1_WRITE}") (class "Default")
      (node (ref "U2") (pin "12") (pinfunction "Y3_12") (pintype "output"))
      (node (ref "U26") (pin "11") (pinfunction "CLK_11") (pintype "input"))
    )
    (net (code "297") (name "~{HALT}") (class "Default")
      (node (ref "R2") (pin "1") (pinfunction "1_1") (pintype "passive"))
      (node (ref "U17") (pin "8") (pinfunction "O_8") (pintype "output"))
      (node (ref "U8") (pin "15") (pinfunction "A3_15") (pintype "input"))
    )
    (net (code "298") (name "~{IOSEL}") (class "Default")
      (node (ref "U25") (pin "2") (pinfunction "A1_2") (pintype "input"))
      (node (ref "U6") (pin "19") (pinfunction "P=Q_19") (pintype "output"))
    )
    (net (code "299") (name "~{IVP}") (class "Default")
      (node (ref "U16") (pin "1") (pinfunction "OC_1") (pintype "input"))
      (node (ref "U18") (pin "4") (pinfunction "I0_4") (pintype "input"))
      (node (ref "U22") (pin "9") (pinfunction "Y6_9") (pintype "output"))
    )
    (net (code "300") (name "~{MLB}") (class "Default")
      (node (ref "U18") (pin "2") (pinfunction "I1_2") (pintype "input"))
      (node (ref "U20") (pin "5") (pinfunction "~{MLB}_5") (pintype "output"))
    )
    (net (code "301") (name "~{RD}") (class "Default")
      (node (ref "U17") (pin "3") (pinfunction "O_3") (pintype "output"))
      (node (ref "U22") (pin "5") (pinfunction "G2B_5") (pintype "input"))
      (node (ref "U8") (pin "2") (pinfunction "A1_2") (pintype "input"))
    )
    (net (code "302") (name "~{RST}") (class "Default")
      (node (ref "U10") (pin "4") (pinfunction "PRE_4") (pintype "input"))
      (node (ref "U11") (pin "1") (pinfunction "CLR_1") (pintype "input"))
      (node (ref "U18") (pin "5") (pinfunction "I1_5") (pintype "input"))
      (node (ref "U20") (pin "40") (pinfunction "~{RESB}_40") (pintype "input"))
      (node (ref "U26") (pin "1") (pinfunction "CLR_1") (pintype "input"))
      (node (ref "U8") (pin "9") (pinfunction "Y1_9") (pintype "tri_state"))
      (node (ref "U9") (pin "1") (pinfunction "CLR_1") (pintype "input"))
      (node (ref "U9") (pin "13") (pinfunction "CLR_13") (pintype "input"))
    )
    (net (code "303") (name "~{VINT}") (class "Default")
      (node (ref "U18") (pin "9") (pinfunction "I0_9") (pintype "input"))
      (node (ref "U23") (pin "14") (pinfunction "GS_14") (pintype "output"))
    )
    (net (code "304") (name "~{VPB}") (class "Default")
      (node (ref "JP3") (pin "2") (pinfunction "2_2") (pintype "passive"))
      (node (ref "U19") (pin "5") (pinfunction "I_5") (pintype "input"))
      (node (ref "U20") (pin "1") (pinfunction "~{VPB}_1") (pintype "output"))
      (node (ref "U22") (pin "4") (pinfunction "G2A_4") (pintype "input"))
    )
    (net (code "305") (name "~{WAIT_DMA}") (class "Default")
      (node (ref "U3") (pin "5") (pinfunction "I1_5") (pintype "input"))
      (node (ref "U9") (pin "8") (pinfunction "~{Q}_8") (pintype "output"))
    )
    (net (code "306") (name "~{WR}") (class "Default")
      (node (ref "U17") (pin "6") (pinfunction "O_6") (pintype "output"))
      (node (ref "U8") (pin "4") (pinfunction "A2_4") (pintype "input"))
    )
  )
)
